# Testing_board_CIDIC_rev_aamaya.net
KiCad netlist of a schematic drawn in EAGLE
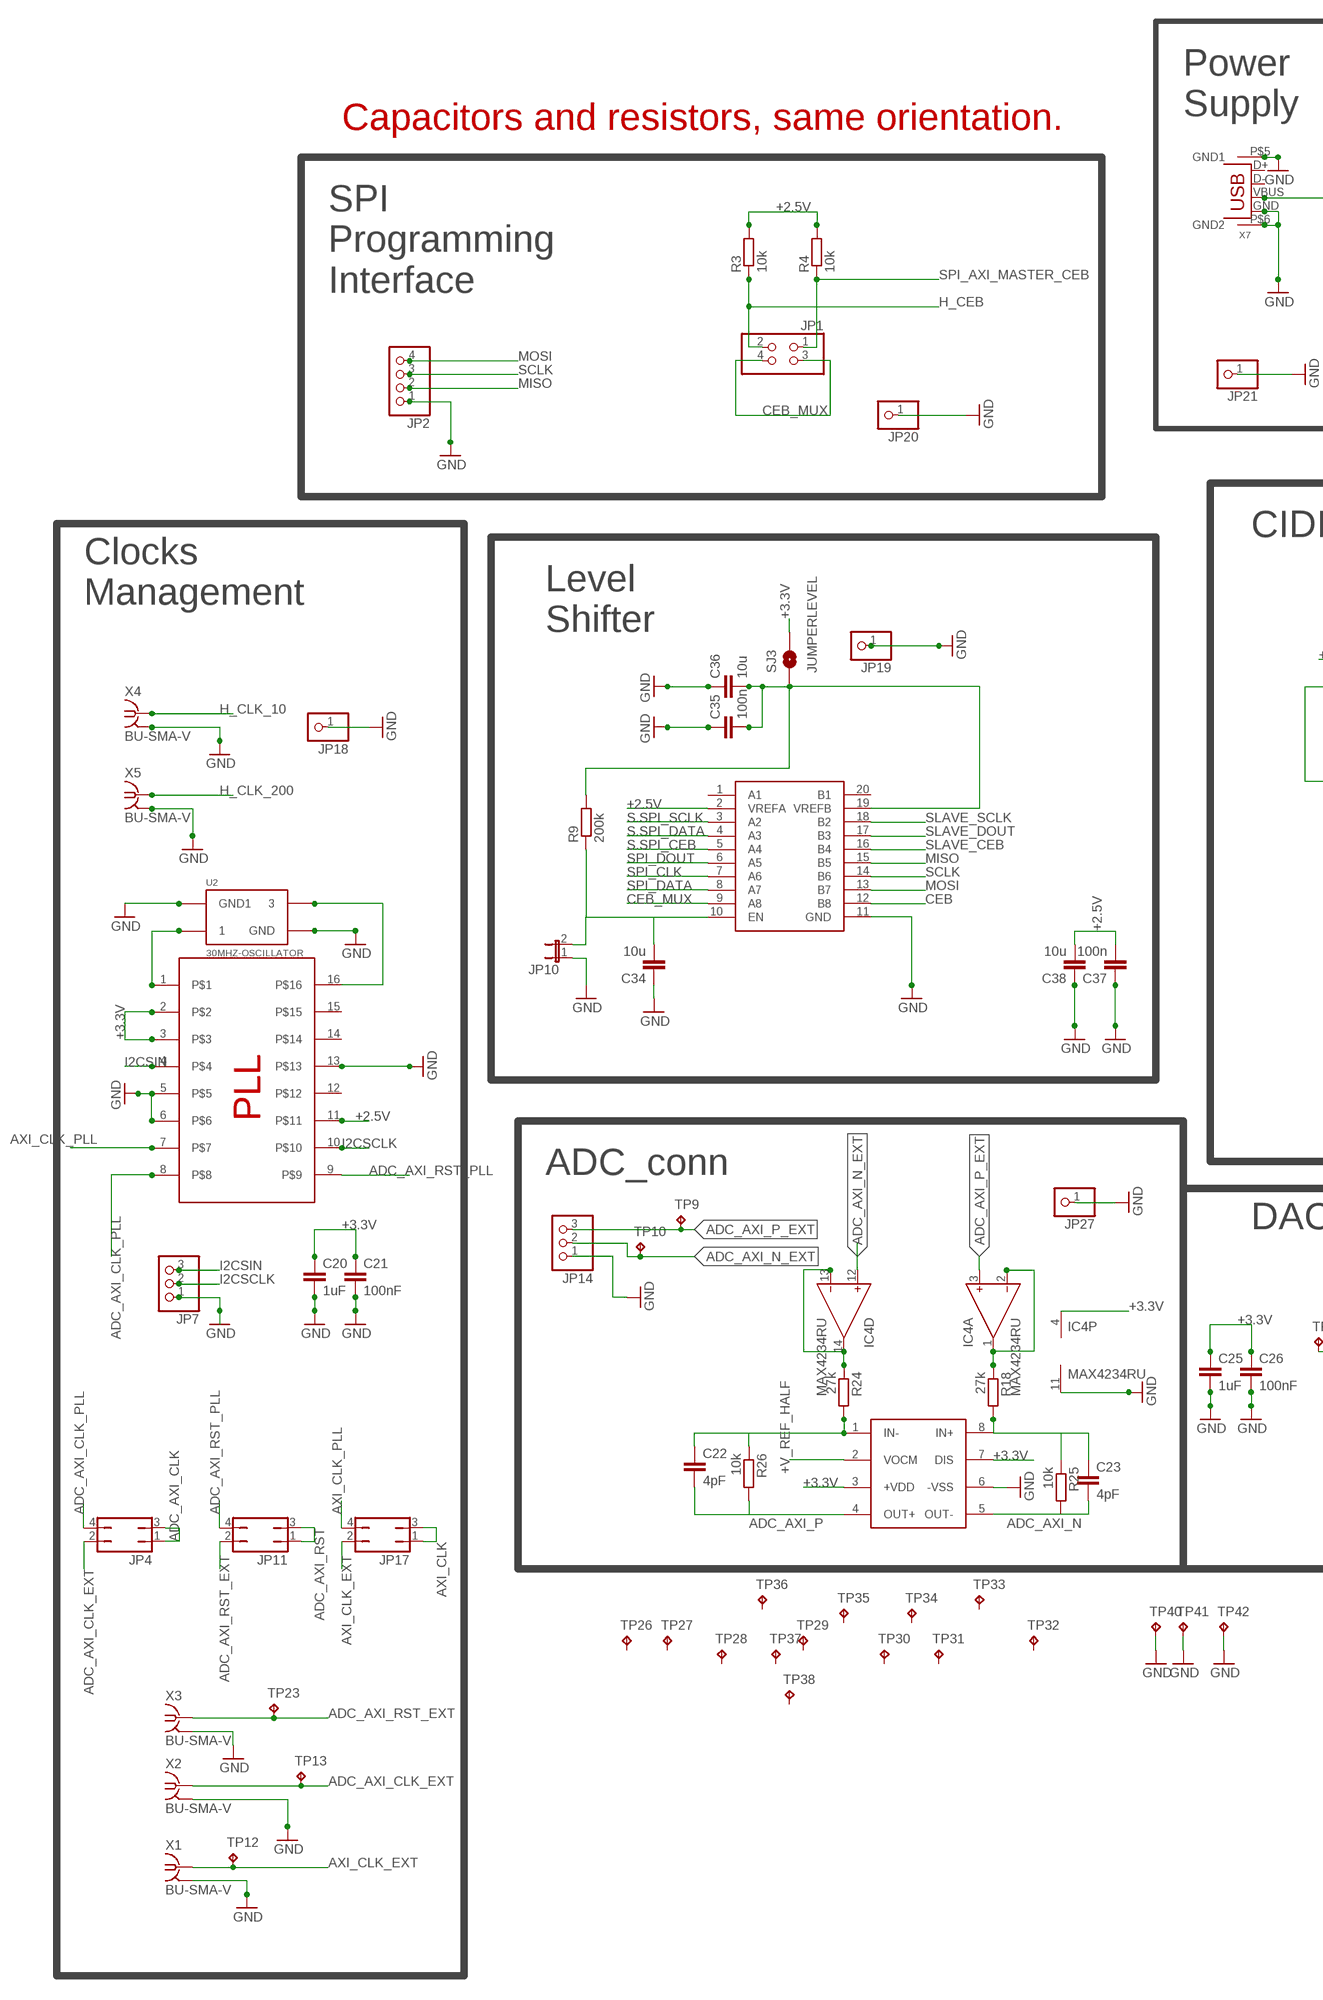
[diagram p0: schematic, sheet 1, part 1 of 2]
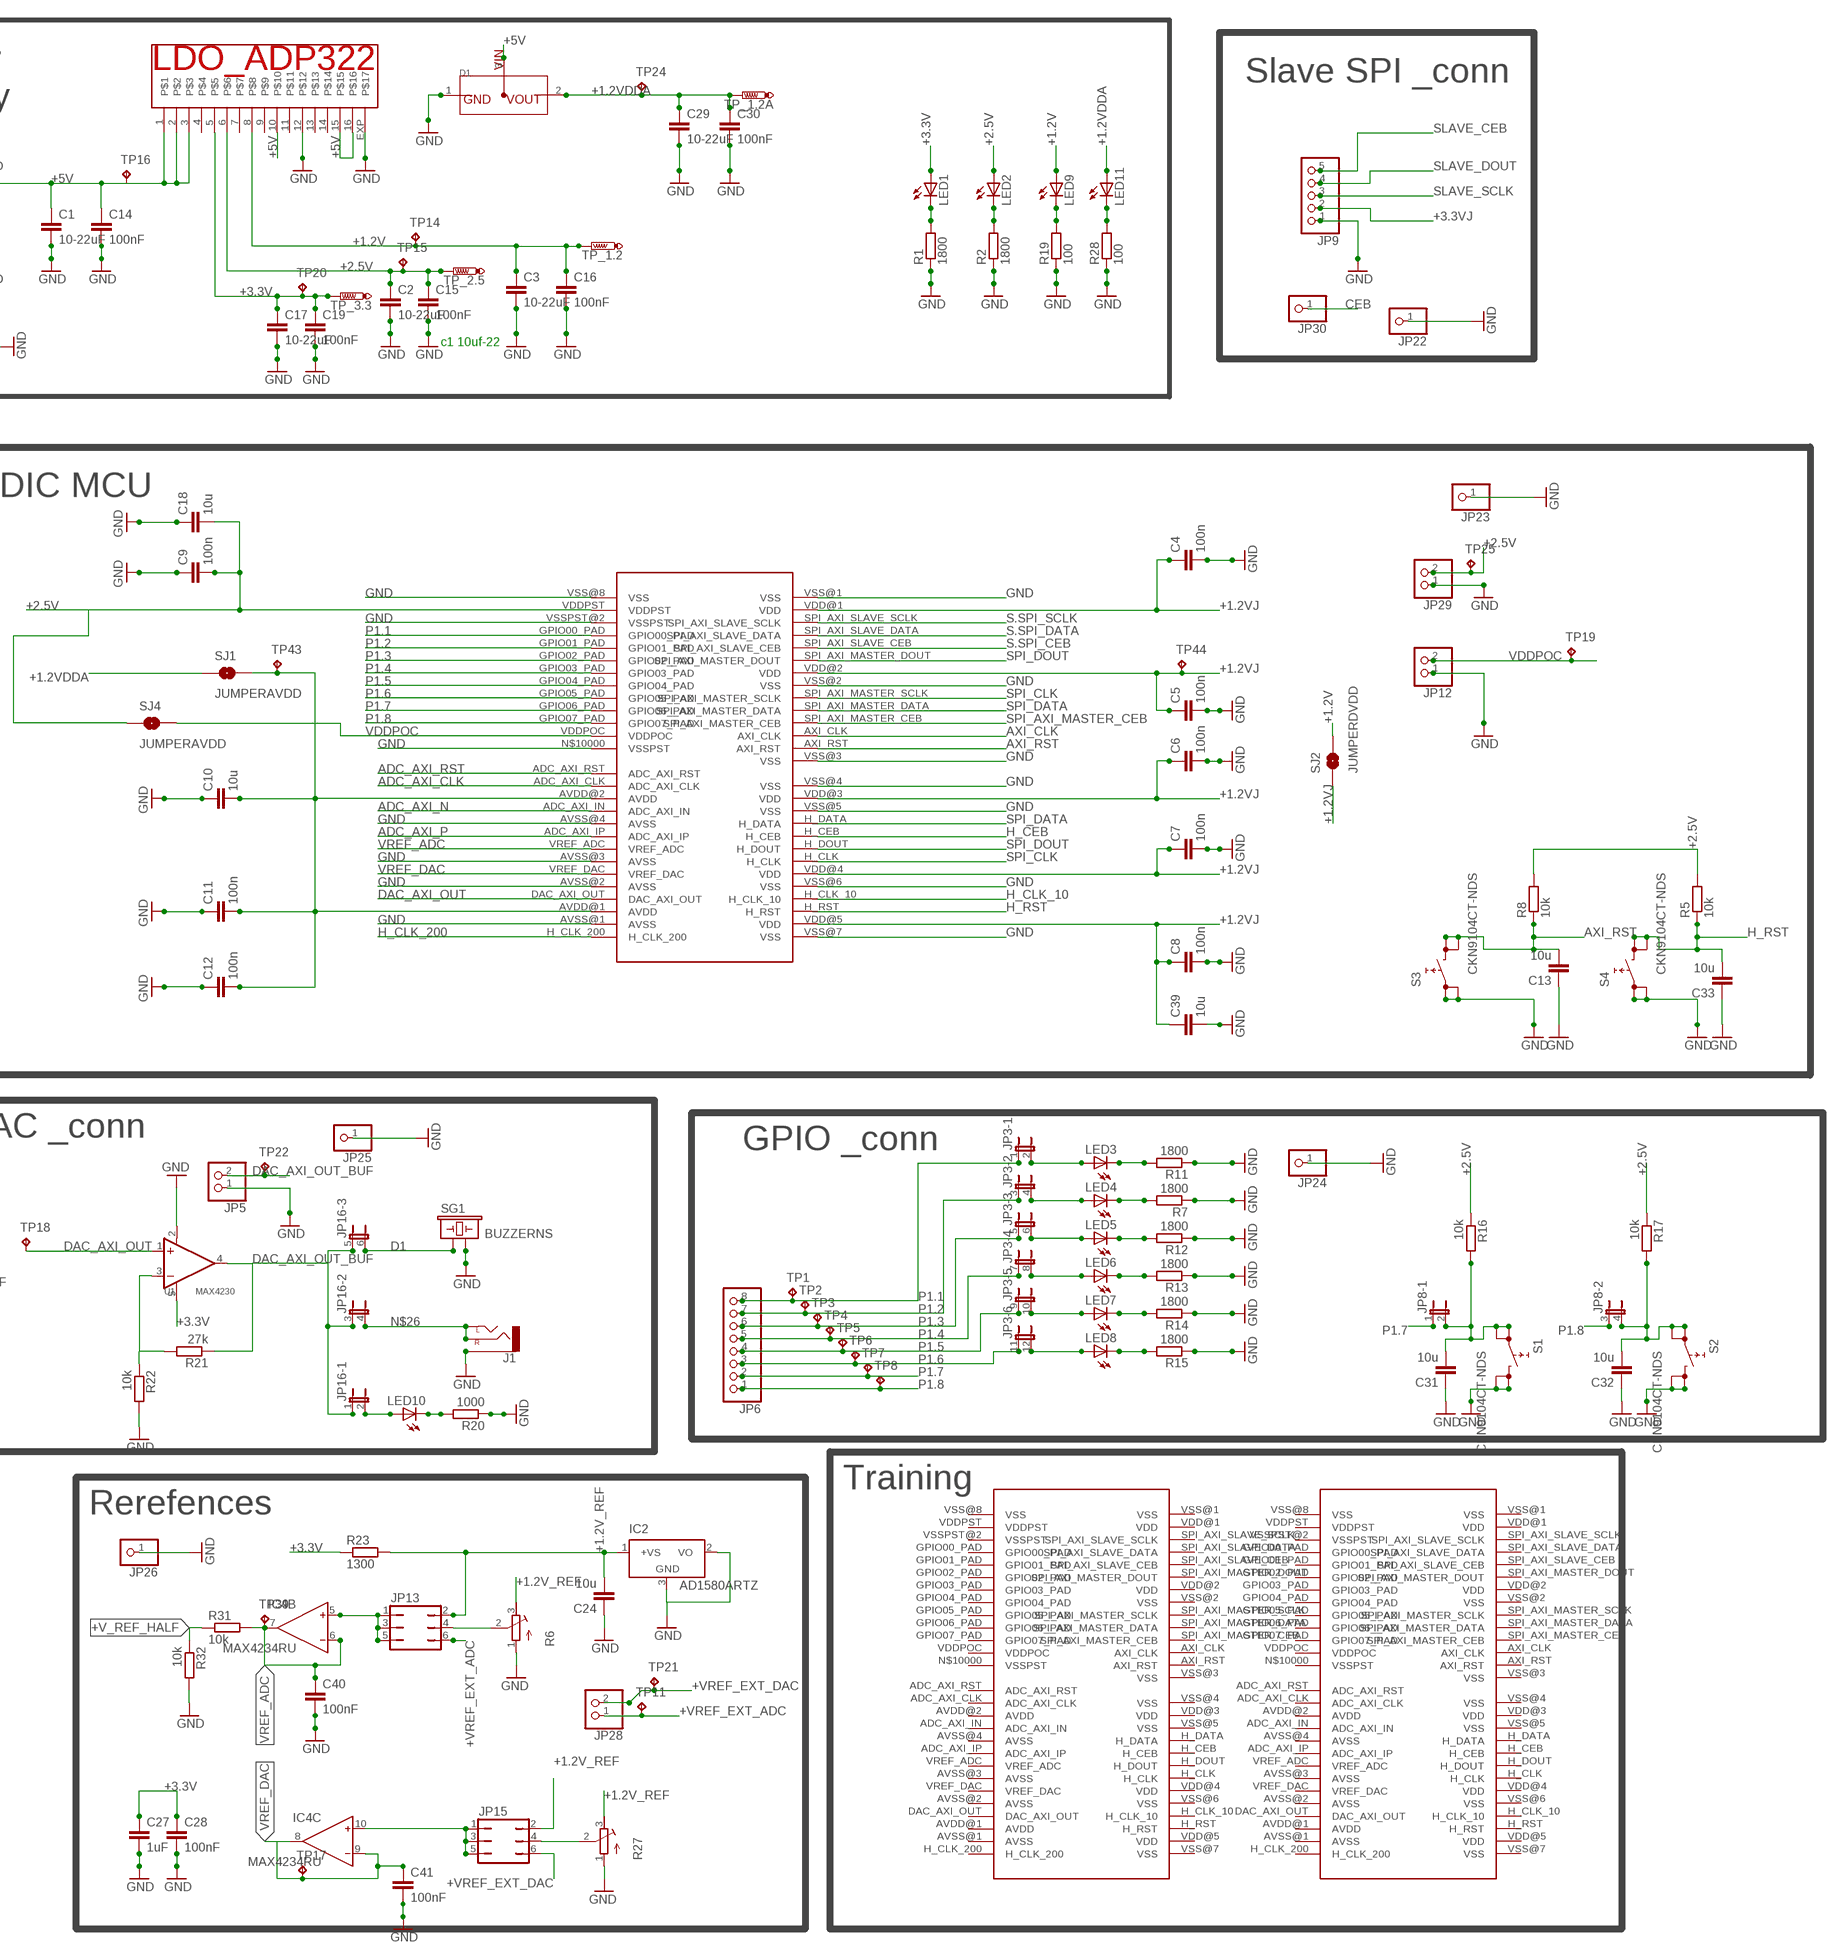
[diagram p1: schematic, sheet 1, part 2 of 2]

(export (version "E")
  (design (tool "Eeschema 10.0.6"))
  (components
    (comp (ref "C1")
      (value "10-22uF")
      (footprint "eagle-import:C0603")
      (libsource (lib "eagle-import") (part "C-EUC0603"))
    )
    (comp (ref "C2")
      (value "10-22uF")
      (footprint "eagle-import:C0603")
      (libsource (lib "eagle-import") (part "C-EUC0603"))
    )
    (comp (ref "C3")
      (value "10-22uF")
      (footprint "eagle-import:C0603")
      (libsource (lib "eagle-import") (part "C-EUC0603"))
    )
    (comp (ref "C4")
      (value "100n")
      (footprint "eagle-import:C0603")
      (libsource (lib "eagle-import") (part "C-EUC0603"))
    )
    (comp (ref "C5")
      (value "100n")
      (footprint "eagle-import:C0603")
      (libsource (lib "eagle-import") (part "C-EUC0603"))
    )
    (comp (ref "C6")
      (value "100n")
      (footprint "eagle-import:C0603")
      (libsource (lib "eagle-import") (part "C-EUC0603"))
    )
    (comp (ref "C7")
      (value "100n")
      (footprint "eagle-import:C0603")
      (libsource (lib "eagle-import") (part "C-EUC0603"))
    )
    (comp (ref "C8")
      (value "100n")
      (footprint "eagle-import:C0603")
      (libsource (lib "eagle-import") (part "C-EUC0603"))
    )
    (comp (ref "C9")
      (value "100n")
      (footprint "eagle-import:C0603")
      (libsource (lib "eagle-import") (part "C-EUC0603"))
    )
    (comp (ref "C10")
      (value "10u")
      (footprint "eagle-import:C0603")
      (libsource (lib "eagle-import") (part "C-EUC0603"))
    )
    (comp (ref "C11")
      (value "100n")
      (footprint "eagle-import:C0603")
      (libsource (lib "eagle-import") (part "C-EUC0603"))
    )
    (comp (ref "C12")
      (value "100n")
      (footprint "eagle-import:C0603")
      (libsource (lib "eagle-import") (part "C-EUC0603"))
    )
    (comp (ref "C13")
      (value "10u")
      (footprint "eagle-import:C0603")
      (libsource (lib "eagle-import") (part "C-EUC0603"))
    )
    (comp (ref "C14")
      (value "100nF")
      (footprint "eagle-import:C0603")
      (libsource (lib "eagle-import") (part "C-EUC0603"))
    )
    (comp (ref "C15")
      (value "100nF")
      (footprint "eagle-import:C0603")
      (libsource (lib "eagle-import") (part "C-EUC0603"))
    )
    (comp (ref "C16")
      (value "100nF")
      (footprint "eagle-import:C0603")
      (libsource (lib "eagle-import") (part "C-EUC0603"))
    )
    (comp (ref "C17")
      (value "10-22uF")
      (footprint "eagle-import:C0603")
      (libsource (lib "eagle-import") (part "C-EUC0603"))
    )
    (comp (ref "C18")
      (value "10u")
      (footprint "eagle-import:C0603")
      (libsource (lib "eagle-import") (part "C-EUC0603"))
    )
    (comp (ref "C19")
      (value "100nF")
      (footprint "eagle-import:C0603")
      (libsource (lib "eagle-import") (part "C-EUC0603"))
    )
    (comp (ref "C20")
      (value "1uF")
      (footprint "eagle-import:C0603")
      (libsource (lib "eagle-import") (part "C-EUC0603"))
    )
    (comp (ref "C21")
      (value "100nF")
      (footprint "eagle-import:C0603")
      (libsource (lib "eagle-import") (part "C-EUC0603"))
    )
    (comp (ref "C22")
      (value "4pF")
      (footprint "eagle-import:C0603")
      (libsource (lib "eagle-import") (part "C-EUC0603"))
    )
    (comp (ref "C23")
      (value "4pF")
      (footprint "eagle-import:C0603")
      (libsource (lib "eagle-import") (part "C-EUC0603"))
    )
    (comp (ref "C24")
      (value "10u")
      (footprint "eagle-import:C0603")
      (libsource (lib "eagle-import") (part "C-EUC0603"))
    )
    (comp (ref "C25")
      (value "1uF")
      (footprint "eagle-import:C0603")
      (libsource (lib "eagle-import") (part "C-EUC0603"))
    )
    (comp (ref "C26")
      (value "100nF")
      (footprint "eagle-import:C0603")
      (libsource (lib "eagle-import") (part "C-EUC0603"))
    )
    (comp (ref "C27")
      (value "1uF")
      (footprint "eagle-import:C0603")
      (libsource (lib "eagle-import") (part "C-EUC0603"))
    )
    (comp (ref "C28")
      (value "100nF")
      (footprint "eagle-import:C0603")
      (libsource (lib "eagle-import") (part "C-EUC0603"))
    )
    (comp (ref "C29")
      (value "10-22uF")
      (footprint "eagle-import:C0603")
      (libsource (lib "eagle-import") (part "C-EUC0603"))
    )
    (comp (ref "C30")
      (value "100nF")
      (footprint "eagle-import:C0603")
      (libsource (lib "eagle-import") (part "C-EUC0603"))
    )
    (comp (ref "C31")
      (value "10u")
      (footprint "eagle-import:C0603")
      (libsource (lib "eagle-import") (part "C-EUC0603"))
    )
    (comp (ref "C32")
      (value "10u")
      (footprint "eagle-import:C0603")
      (libsource (lib "eagle-import") (part "C-EUC0603"))
    )
    (comp (ref "C33")
      (value "10u")
      (footprint "eagle-import:C0603")
      (libsource (lib "eagle-import") (part "C-EUC0603"))
    )
    (comp (ref "C34")
      (value "10u")
      (footprint "eagle-import:C0603")
      (libsource (lib "eagle-import") (part "C-EUC0603"))
    )
    (comp (ref "C35")
      (value "100n")
      (footprint "eagle-import:C0603")
      (libsource (lib "eagle-import") (part "C-EUC0603"))
    )
    (comp (ref "C36")
      (value "10u")
      (footprint "eagle-import:C0603")
      (libsource (lib "eagle-import") (part "C-EUC0603"))
    )
    (comp (ref "C37")
      (value "100n")
      (footprint "eagle-import:C0603")
      (libsource (lib "eagle-import") (part "C-EUC0603"))
    )
    (comp (ref "C38")
      (value "10u")
      (footprint "eagle-import:C0603")
      (libsource (lib "eagle-import") (part "C-EUC0603"))
    )
    (comp (ref "C39")
      (value "10u")
      (footprint "eagle-import:C0603")
      (libsource (lib "eagle-import") (part "C-EUC0603"))
    )
    (comp (ref "C40")
      (value "100nF")
      (footprint "eagle-import:C0603")
      (libsource (lib "eagle-import") (part "C-EUC0603"))
    )
    (comp (ref "C41")
      (value "100nF")
      (footprint "eagle-import:C0603")
      (libsource (lib "eagle-import") (part "C-EUC0603"))
    )
    (comp (ref "D1")
      (value "MCP1700T-1202E/TTCT-ND")
      (footprint "eagle-import:SOT-23")
      (libsource (lib "eagle-import") (part "MCP1700T-1202E/TTCT-ND"))
    )
    (comp (ref "GND")
      (value "ADP322")
      (footprint "eagle-import:LFCSP_LQ-16")
      (libsource (lib "eagle-import") (part "ADP322"))
    )
    (comp (ref "IC2")
      (value "AD1580ARTZ")
      (footprint "eagle-import:SOT23")
      (libsource (lib "eagle-import") (part "LM50"))
    )
    (comp (ref "IC4")
      (value "MAX4234RU")
      (footprint "eagle-import:TSSOP14")
      (fields (field (name "MF") "ALTERA CORPORATION") (field (name "MPN") "AD8609ARUZ"))
      (libsource (lib "eagle-import") (part "MAX4234RU"))
    )
    (comp (ref "J1")
      (value "AUDIO-JACK_DIGIKEYSMD")
      (footprint "eagle-import:STEREOJACK2.5MM_SMD")
      (libsource (lib "eagle-import") (part "AUDIO-JACK_DIGIKEYSMD"))
    )
    (comp (ref "JP1")
      (value "PINHD-2X2")
      (footprint "eagle-import:2X02")
      (libsource (lib "eagle-import") (part "PINHD-2X2"))
    )
    (comp (ref "JP2")
      (value "PINHD-1X4")
      (footprint "eagle-import:1X04")
      (libsource (lib "eagle-import") (part "PINHD-1X4"))
    )
    (comp (ref "JP3")
      (value "JP6QE")
      (footprint "eagle-import:JP6Q")
      (libsource (lib "eagle-import") (part "JP6QE"))
    )
    (comp (ref "JP4")
      (value "JP2Q")
      (footprint "eagle-import:JP2Q")
      (libsource (lib "eagle-import") (part "JP2Q"))
    )
    (comp (ref "JP5")
      (value "PINHD-1X2")
      (footprint "eagle-import:1X02")
      (libsource (lib "eagle-import") (part "PINHD-1X2"))
    )
    (comp (ref "JP6")
      (value "PINHD-1X8")
      (footprint "eagle-import:1X08")
      (libsource (lib "eagle-import") (part "PINHD-1X8"))
    )
    (comp (ref "JP7")
      (value "PINHD-1X3")
      (footprint "eagle-import:1X03")
      (libsource (lib "eagle-import") (part "PINHD-1X3"))
    )
    (comp (ref "JP8")
      (value "JP2QE")
      (footprint "eagle-import:JP2Q")
      (libsource (lib "eagle-import") (part "JP2QE"))
    )
    (comp (ref "JP9")
      (value "PINHD-1X5")
      (footprint "eagle-import:1X05")
      (libsource (lib "eagle-import") (part "PINHD-1X5"))
    )
    (comp (ref "JP10")
      (value "JP1E")
      (footprint "eagle-import:JP1")
      (libsource (lib "eagle-import") (part "JP1E"))
    )
    (comp (ref "JP11")
      (value "JP2Q")
      (footprint "eagle-import:JP2Q")
      (libsource (lib "eagle-import") (part "JP2Q"))
    )
    (comp (ref "JP12")
      (value "PINHD-1X2")
      (footprint "eagle-import:1X02")
      (libsource (lib "eagle-import") (part "PINHD-1X2"))
    )
    (comp (ref "JP13")
      (value "JP3Q")
      (footprint "eagle-import:JP3Q")
      (libsource (lib "eagle-import") (part "JP3Q"))
    )
    (comp (ref "JP14")
      (value "PINHD-1X3")
      (footprint "eagle-import:1X03")
      (libsource (lib "eagle-import") (part "PINHD-1X3"))
    )
    (comp (ref "JP15")
      (value "JP3Q")
      (footprint "eagle-import:JP3Q")
      (libsource (lib "eagle-import") (part "JP3Q"))
    )
    (comp (ref "JP16")
      (value "JP3QE")
      (footprint "eagle-import:JP3Q")
      (libsource (lib "eagle-import") (part "JP3QE"))
    )
    (comp (ref "JP17")
      (value "JP2Q")
      (footprint "eagle-import:JP2Q")
      (libsource (lib "eagle-import") (part "JP2Q"))
    )
    (comp (ref "JP18")
      (value "PINHD-1X1")
      (footprint "eagle-import:1X01")
      (libsource (lib "eagle-import") (part "PINHD-1X1"))
    )
    (comp (ref "JP19")
      (value "PINHD-1X1")
      (footprint "eagle-import:1X01")
      (libsource (lib "eagle-import") (part "PINHD-1X1"))
    )
    (comp (ref "JP20")
      (value "PINHD-1X1")
      (footprint "eagle-import:1X01")
      (libsource (lib "eagle-import") (part "PINHD-1X1"))
    )
    (comp (ref "JP21")
      (value "PINHD-1X1")
      (footprint "eagle-import:1X01")
      (libsource (lib "eagle-import") (part "PINHD-1X1"))
    )
    (comp (ref "JP22")
      (value "PINHD-1X1")
      (footprint "eagle-import:1X01")
      (libsource (lib "eagle-import") (part "PINHD-1X1"))
    )
    (comp (ref "JP23")
      (value "PINHD-1X1")
      (footprint "eagle-import:1X01")
      (libsource (lib "eagle-import") (part "PINHD-1X1"))
    )
    (comp (ref "JP24")
      (value "PINHD-1X1")
      (footprint "eagle-import:1X01")
      (libsource (lib "eagle-import") (part "PINHD-1X1"))
    )
    (comp (ref "JP25")
      (value "PINHD-1X1")
      (footprint "eagle-import:1X01")
      (libsource (lib "eagle-import") (part "PINHD-1X1"))
    )
    (comp (ref "JP26")
      (value "PINHD-1X1")
      (footprint "eagle-import:1X01")
      (libsource (lib "eagle-import") (part "PINHD-1X1"))
    )
    (comp (ref "JP27")
      (value "PINHD-1X1")
      (footprint "eagle-import:1X01")
      (libsource (lib "eagle-import") (part "PINHD-1X1"))
    )
    (comp (ref "JP28")
      (value "PINHD-1X2")
      (footprint "eagle-import:1X02")
      (libsource (lib "eagle-import") (part "PINHD-1X2"))
    )
    (comp (ref "JP29")
      (value "PINHD-1X2")
      (footprint "eagle-import:1X02")
      (libsource (lib "eagle-import") (part "PINHD-1X2"))
    )
    (comp (ref "JP30")
      (value "PINHD-1X1")
      (footprint "eagle-import:1X01")
      (libsource (lib "eagle-import") (part "PINHD-1X1"))
    )
    (comp (ref "LED1")
      (value "LEDSML0805")
      (footprint "eagle-import:SML0805")
      (libsource (lib "eagle-import") (part "LEDSML0805"))
    )
    (comp (ref "LED2")
      (value "LEDSML0805")
      (footprint "eagle-import:SML0805")
      (libsource (lib "eagle-import") (part "LEDSML0805"))
    )
    (comp (ref "LED3")
      (value "LEDCHIPLED_0805")
      (footprint "eagle-import:CHIPLED_0805")
      (libsource (lib "eagle-import") (part "LEDCHIPLED_0805"))
    )
    (comp (ref "LED4")
      (value "LEDCHIPLED_0805")
      (footprint "eagle-import:CHIPLED_0805")
      (libsource (lib "eagle-import") (part "LEDCHIPLED_0805"))
    )
    (comp (ref "LED5")
      (value "LEDCHIPLED_0805")
      (footprint "eagle-import:CHIPLED_0805")
      (libsource (lib "eagle-import") (part "LEDCHIPLED_0805"))
    )
    (comp (ref "LED6")
      (value "LEDCHIPLED_0805")
      (footprint "eagle-import:CHIPLED_0805")
      (libsource (lib "eagle-import") (part "LEDCHIPLED_0805"))
    )
    (comp (ref "LED7")
      (value "LEDCHIPLED_0805")
      (footprint "eagle-import:CHIPLED_0805")
      (libsource (lib "eagle-import") (part "LEDCHIPLED_0805"))
    )
    (comp (ref "LED8")
      (value "LEDCHIPLED_0805")
      (footprint "eagle-import:CHIPLED_0805")
      (libsource (lib "eagle-import") (part "LEDCHIPLED_0805"))
    )
    (comp (ref "LED9")
      (value "LEDSML0805")
      (footprint "eagle-import:SML0805")
      (libsource (lib "eagle-import") (part "LEDSML0805"))
    )
    (comp (ref "LED10")
      (value "LEDSML0805")
      (footprint "eagle-import:SML0805")
      (libsource (lib "eagle-import") (part "LEDSML0805"))
    )
    (comp (ref "LED11")
      (value "LEDSML0805")
      (footprint "eagle-import:SML0805")
      (libsource (lib "eagle-import") (part "LEDSML0805"))
    )
    (comp (ref "R1")
      (value "1800")
      (footprint "eagle-import:R0603")
      (libsource (lib "eagle-import") (part "R-EU_R0603"))
    )
    (comp (ref "R2")
      (value "1800")
      (footprint "eagle-import:R0603")
      (libsource (lib "eagle-import") (part "R-EU_R0603"))
    )
    (comp (ref "R3")
      (value "10k")
      (footprint "eagle-import:R0603")
      (libsource (lib "eagle-import") (part "R-EU_R0603"))
    )
    (comp (ref "R4")
      (value "10k")
      (footprint "eagle-import:R0603")
      (libsource (lib "eagle-import") (part "R-EU_R0603"))
    )
    (comp (ref "R5")
      (value "10k")
      (footprint "eagle-import:R0603")
      (libsource (lib "eagle-import") (part "R-EU_R0603"))
    )
    (comp (ref "R6")
      (value "R-TRIMM4G/J")
      (footprint "eagle-import:RTRIM4G_J")
      (libsource (lib "eagle-import") (part "R-TRIMM4G/J"))
    )
    (comp (ref "R7")
      (value "1800")
      (footprint "eagle-import:R0603")
      (libsource (lib "eagle-import") (part "R-EU_R0603"))
    )
    (comp (ref "R8")
      (value "10k")
      (footprint "eagle-import:R0603")
      (libsource (lib "eagle-import") (part "R-EU_R0603"))
    )
    (comp (ref "R9")
      (value "200k")
      (footprint "eagle-import:R0603")
      (libsource (lib "eagle-import") (part "R-EU_R0603"))
    )
    (comp (ref "R11")
      (value "1800")
      (footprint "eagle-import:R0603")
      (libsource (lib "eagle-import") (part "R-EU_R0603"))
    )
    (comp (ref "R12")
      (value "1800")
      (footprint "eagle-import:R0603")
      (libsource (lib "eagle-import") (part "R-EU_R0603"))
    )
    (comp (ref "R13")
      (value "1800")
      (footprint "eagle-import:R0603")
      (libsource (lib "eagle-import") (part "R-EU_R0603"))
    )
    (comp (ref "R14")
      (value "1800")
      (footprint "eagle-import:R0603")
      (libsource (lib "eagle-import") (part "R-EU_R0603"))
    )
    (comp (ref "R15")
      (value "1800")
      (footprint "eagle-import:R0603")
      (libsource (lib "eagle-import") (part "R-EU_R0603"))
    )
    (comp (ref "R16")
      (value "10k")
      (footprint "eagle-import:R0603")
      (libsource (lib "eagle-import") (part "R-EU_R0603"))
    )
    (comp (ref "R17")
      (value "10k")
      (footprint "eagle-import:R0603")
      (libsource (lib "eagle-import") (part "R-EU_R0603"))
    )
    (comp (ref "R18")
      (value "27k")
      (footprint "eagle-import:R0603")
      (libsource (lib "eagle-import") (part "R-EU_R0603"))
    )
    (comp (ref "R19")
      (value "100")
      (footprint "eagle-import:R0603")
      (libsource (lib "eagle-import") (part "R-EU_R0603"))
    )
    (comp (ref "R20")
      (value "1000")
      (footprint "eagle-import:R0603")
      (libsource (lib "eagle-import") (part "R-EU_R0603"))
    )
    (comp (ref "R21")
      (value "27k")
      (footprint "eagle-import:R0603")
      (libsource (lib "eagle-import") (part "R-EU_R0603"))
    )
    (comp (ref "R22")
      (value "10k")
      (footprint "eagle-import:R0603")
      (libsource (lib "eagle-import") (part "R-EU_R0603"))
    )
    (comp (ref "R23")
      (value "1300")
      (footprint "eagle-import:R0603")
      (libsource (lib "eagle-import") (part "R-EU_R0603"))
    )
    (comp (ref "R24")
      (value "27k")
      (footprint "eagle-import:R0603")
      (libsource (lib "eagle-import") (part "R-EU_R0603"))
    )
    (comp (ref "R25")
      (value "10k")
      (footprint "eagle-import:R0603")
      (libsource (lib "eagle-import") (part "R-EU_R0603"))
    )
    (comp (ref "R26")
      (value "10k")
      (footprint "eagle-import:R0603")
      (libsource (lib "eagle-import") (part "R-EU_R0603"))
    )
    (comp (ref "R27")
      (value "R-TRIMM4G/J")
      (footprint "eagle-import:RTRIM4G_J")
      (libsource (lib "eagle-import") (part "R-TRIMM4G/J"))
    )
    (comp (ref "R28")
      (value "100")
      (footprint "eagle-import:R0603")
      (libsource (lib "eagle-import") (part "R-EU_R0603"))
    )
    (comp (ref "R31")
      (value "10k")
      (footprint "eagle-import:R0603")
      (libsource (lib "eagle-import") (part "R-EU_R0603"))
    )
    (comp (ref "R32")
      (value "10k")
      (footprint "eagle-import:R0603")
      (libsource (lib "eagle-import") (part "R-EU_R0603"))
    )
    (comp (ref "S1")
      (value "CKN9104CT-NDS")
      (footprint "eagle-import:SKHMPXE010")
      (libsource (lib "eagle-import") (part "CKN9104CT-NDS"))
    )
    (comp (ref "S2")
      (value "CKN9104CT-NDS")
      (footprint "eagle-import:SKHMPXE010")
      (libsource (lib "eagle-import") (part "CKN9104CT-NDS"))
    )
    (comp (ref "S3")
      (value "CKN9104CT-NDS")
      (footprint "eagle-import:SKHMPXE010")
      (libsource (lib "eagle-import") (part "CKN9104CT-NDS"))
    )
    (comp (ref "S4")
      (value "CKN9104CT-NDS")
      (footprint "eagle-import:SKHMPXE010")
      (libsource (lib "eagle-import") (part "CKN9104CT-NDS"))
    )
    (comp (ref "SG1")
      (value "BUZZERNS")
      (footprint "eagle-import:BUZZER-12MM-NS")
      (libsource (lib "eagle-import") (part "BUZZERNS"))
    )
    (comp (ref "SJ1")
      (value "JUMPERAVDD")
      (footprint "eagle-import:SJ_ROUND")
      (libsource (lib "eagle-import") (part "SOLDERJUMPERROUND"))
    )
    (comp (ref "SJ2")
      (value "JUMPERDVDD")
      (footprint "eagle-import:SJ_ROUND")
      (libsource (lib "eagle-import") (part "SOLDERJUMPERROUND"))
    )
    (comp (ref "SJ3")
      (value "JUMPERLEVEL")
      (footprint "eagle-import:SJ_ROUND")
      (libsource (lib "eagle-import") (part "SOLDERJUMPERROUND"))
    )
    (comp (ref "SJ4")
      (value "JUMPERAVDD")
      (footprint "eagle-import:SJ_ROUND")
      (libsource (lib "eagle-import") (part "SOLDERJUMPERROUND"))
    )
    (comp (ref "TP1")
      (value "TPTP20R")
      (footprint "eagle-import:TP20R")
      (libsource (lib "eagle-import") (part "TPTP20R"))
    )
    (comp (ref "TP2")
      (value "TPTP20R")
      (footprint "eagle-import:TP20R")
      (libsource (lib "eagle-import") (part "TPTP20R"))
    )
    (comp (ref "TP3")
      (value "TPTP20R")
      (footprint "eagle-import:TP20R")
      (libsource (lib "eagle-import") (part "TPTP20R"))
    )
    (comp (ref "TP4")
      (value "TPTP20R")
      (footprint "eagle-import:TP20R")
      (libsource (lib "eagle-import") (part "TPTP20R"))
    )
    (comp (ref "TP5")
      (value "TPTP20R")
      (footprint "eagle-import:TP20R")
      (libsource (lib "eagle-import") (part "TPTP20R"))
    )
    (comp (ref "TP6")
      (value "TPTP20R")
      (footprint "eagle-import:TP20R")
      (libsource (lib "eagle-import") (part "TPTP20R"))
    )
    (comp (ref "TP7")
      (value "TPTP20R")
      (footprint "eagle-import:TP20R")
      (libsource (lib "eagle-import") (part "TPTP20R"))
    )
    (comp (ref "TP8")
      (value "TPTP20R")
      (footprint "eagle-import:TP20R")
      (libsource (lib "eagle-import") (part "TPTP20R"))
    )
    (comp (ref "TP9")
      (value "TPTP20R")
      (footprint "eagle-import:TP20R")
      (libsource (lib "eagle-import") (part "TPTP20R"))
    )
    (comp (ref "TP10")
      (value "TPTP20R")
      (footprint "eagle-import:TP20R")
      (libsource (lib "eagle-import") (part "TPTP20R"))
    )
    (comp (ref "TP11")
      (value "TPTP20R")
      (footprint "eagle-import:TP20R")
      (libsource (lib "eagle-import") (part "TPTP20R"))
    )
    (comp (ref "TP12")
      (value "TPTP20R")
      (footprint "eagle-import:TP20R")
      (libsource (lib "eagle-import") (part "TPTP20R"))
    )
    (comp (ref "TP13")
      (value "TPTP20R")
      (footprint "eagle-import:TP20R")
      (libsource (lib "eagle-import") (part "TPTP20R"))
    )
    (comp (ref "TP14")
      (value "TPTP20R")
      (footprint "eagle-import:TP20R")
      (libsource (lib "eagle-import") (part "TPTP20R"))
    )
    (comp (ref "TP15")
      (value "TPTP20R")
      (footprint "eagle-import:TP20R")
      (libsource (lib "eagle-import") (part "TPTP20R"))
    )
    (comp (ref "TP16")
      (value "TPTP20R")
      (footprint "eagle-import:TP20R")
      (libsource (lib "eagle-import") (part "TPTP20R"))
    )
    (comp (ref "TP17")
      (value "TPTP20R")
      (footprint "eagle-import:TP20R")
      (libsource (lib "eagle-import") (part "TPTP20R"))
    )
    (comp (ref "TP18")
      (value "TPTP20R")
      (footprint "eagle-import:TP20R")
      (libsource (lib "eagle-import") (part "TPTP20R"))
    )
    (comp (ref "TP19")
      (value "TPTP20R")
      (footprint "eagle-import:TP20R")
      (libsource (lib "eagle-import") (part "TPTP20R"))
    )
    (comp (ref "TP20")
      (value "TPTP20R")
      (footprint "eagle-import:TP20R")
      (libsource (lib "eagle-import") (part "TPTP20R"))
    )
    (comp (ref "TP21")
      (value "TPTP20R")
      (footprint "eagle-import:TP20R")
      (libsource (lib "eagle-import") (part "TPTP20R"))
    )
    (comp (ref "TP22")
      (value "TPTP20R")
      (footprint "eagle-import:TP20R")
      (libsource (lib "eagle-import") (part "TPTP20R"))
    )
    (comp (ref "TP23")
      (value "TPTP20R")
      (footprint "eagle-import:TP20R")
      (libsource (lib "eagle-import") (part "TPTP20R"))
    )
    (comp (ref "TP24")
      (value "TPTP20R")
      (footprint "eagle-import:TP20R")
      (libsource (lib "eagle-import") (part "TPTP20R"))
    )
    (comp (ref "TP25")
      (value "TPTP20R")
      (footprint "eagle-import:TP20R")
      (libsource (lib "eagle-import") (part "TPTP20R"))
    )
    (comp (ref "TP26")
      (value "TPTP08R")
      (footprint "eagle-import:TP08R")
      (libsource (lib "eagle-import") (part "TPTP08R"))
    )
    (comp (ref "TP27")
      (value "TPTP08R")
      (footprint "eagle-import:TP08R")
      (libsource (lib "eagle-import") (part "TPTP08R"))
    )
    (comp (ref "TP28")
      (value "TPTP08R")
      (footprint "eagle-import:TP08R")
      (libsource (lib "eagle-import") (part "TPTP08R"))
    )
    (comp (ref "TP29")
      (value "TPTP08R")
      (footprint "eagle-import:TP08R")
      (libsource (lib "eagle-import") (part "TPTP08R"))
    )
    (comp (ref "TP30")
      (value "TPTP08R")
      (footprint "eagle-import:TP08R")
      (libsource (lib "eagle-import") (part "TPTP08R"))
    )
    (comp (ref "TP31")
      (value "TPTP08R")
      (footprint "eagle-import:TP08R")
      (libsource (lib "eagle-import") (part "TPTP08R"))
    )
    (comp (ref "TP32")
      (value "TPTP08R")
      (footprint "eagle-import:TP08R")
      (libsource (lib "eagle-import") (part "TPTP08R"))
    )
    (comp (ref "TP33")
      (value "TPTP08R")
      (footprint "eagle-import:TP08R")
      (libsource (lib "eagle-import") (part "TPTP08R"))
    )
    (comp (ref "TP34")
      (value "TPTP08R")
      (footprint "eagle-import:TP08R")
      (libsource (lib "eagle-import") (part "TPTP08R"))
    )
    (comp (ref "TP35")
      (value "TPTP08R")
      (footprint "eagle-import:TP08R")
      (libsource (lib "eagle-import") (part "TPTP08R"))
    )
    (comp (ref "TP36")
      (value "TPTP08R")
      (footprint "eagle-import:TP08R")
      (libsource (lib "eagle-import") (part "TPTP08R"))
    )
    (comp (ref "TP37")
      (value "TPTP08R")
      (footprint "eagle-import:TP08R")
      (libsource (lib "eagle-import") (part "TPTP08R"))
    )
    (comp (ref "TP38")
      (value "TPTP08R")
      (footprint "eagle-import:TP08R")
      (libsource (lib "eagle-import") (part "TPTP08R"))
    )
    (comp (ref "TP39")
      (value "TPTP20R")
      (footprint "eagle-import:TP20R")
      (libsource (lib "eagle-import") (part "TPTP20R"))
    )
    (comp (ref "TP40")
      (value "TPTP20R")
      (footprint "eagle-import:TP20R")
      (libsource (lib "eagle-import") (part "TPTP20R"))
    )
    (comp (ref "TP41")
      (value "TPTP20R")
      (footprint "eagle-import:TP20R")
      (libsource (lib "eagle-import") (part "TPTP20R"))
    )
    (comp (ref "TP42")
      (value "TPTP20R")
      (footprint "eagle-import:TP20R")
      (libsource (lib "eagle-import") (part "TPTP20R"))
    )
    (comp (ref "TP43")
      (value "TPTP20R")
      (footprint "eagle-import:TP20R")
      (libsource (lib "eagle-import") (part "TPTP20R"))
    )
    (comp (ref "TP44")
      (value "TPTP20R")
      (footprint "eagle-import:TP20R")
      (libsource (lib "eagle-import") (part "TPTP20R"))
    )
    (comp (ref "TP_1.2")
      (value "PTR1B1,27")
      (footprint "eagle-import:B1,27")
      (libsource (lib "eagle-import") (part "PTR1B1,27"))
    )
    (comp (ref "TP_1.2A")
      (value "PTR1B1,27")
      (footprint "eagle-import:B1,27")
      (libsource (lib "eagle-import") (part "PTR1B1,27"))
    )
    (comp (ref "TP_2.5")
      (value "PTR1B1,27")
      (footprint "eagle-import:B1,27")
      (libsource (lib "eagle-import") (part "PTR1B1,27"))
    )
    (comp (ref "TP_3.3")
      (value "PTR1B1,27")
      (footprint "eagle-import:B1,27")
      (libsource (lib "eagle-import") (part "PTR1B1,27"))
    )
    (comp (ref "U$1")
      (value "CIDIC_AXI_UC_TEST_DIE")
      (footprint "eagle-import:CIDIC_AXI_UC_TEST_DIE")
      (libsource (lib "eagle-import") (part "CIDIC_AXI_UC_TEST_DIE"))
    )
    (comp (ref "U$3")
      (value "LEVEL_SHIFTER_8")
      (footprint "eagle-import:TSSOP20")
      (libsource (lib "eagle-import") (part "LEVEL_SHIFTER_8"))
    )
    (comp (ref "U$4")
      (value "CY22150KFZXC")
      (footprint "eagle-import:TSSOP16")
      (libsource (lib "eagle-import") (part "CY22150KFZXC"))
    )
    (comp (ref "U$5")
      (value "ADA4940")
      (footprint "eagle-import:SO8")
      (libsource (lib "eagle-import") (part "ADA4940"))
    )
    (comp (ref "U$6")
      (value "CIDIC_AXI_UC_TEST_DIE")
      (footprint "eagle-import:CIDIC_AXI_UC_TEST_DIE")
      (libsource (lib "eagle-import") (part "CIDIC_AXI_UC_TEST_DIE"))
    )
    (comp (ref "U$7")
      (value "CIDIC_AXI_UC_TEST_DIE")
      (footprint "eagle-import:CIDIC_AXI_UC_TEST_DIE")
      (libsource (lib "eagle-import") (part "CIDIC_AXI_UC_TEST_DIE"))
    )
    (comp (ref "U1")
      (value "MAX4230")
      (footprint "eagle-import:SC-70-5")
      (fields (field (name "MPN") "LMV321IDCKR"))
      (libsource (lib "eagle-import") (part "MAX4230"))
    )
    (comp (ref "U2")
      (value "30MHZ-OSCILLATOR")
      (footprint "eagle-import:5X3.2")
      (libsource (lib "eagle-import") (part "30MHZ-OSCILLATOR"))
    )
    (comp (ref "X1")
      (value "BU-SMA-V")
      (footprint "eagle-import:BU-SMA-V")
      (libsource (lib "eagle-import") (part "BU-SMA-V"))
    )
    (comp (ref "X2")
      (value "BU-SMA-V")
      (footprint "eagle-import:BU-SMA-V")
      (libsource (lib "eagle-import") (part "BU-SMA-V"))
    )
    (comp (ref "X3")
      (value "BU-SMA-V")
      (footprint "eagle-import:BU-SMA-V")
      (libsource (lib "eagle-import") (part "BU-SMA-V"))
    )
    (comp (ref "X4")
      (value "BU-SMA-V")
      (footprint "eagle-import:BU-SMA-V")
      (libsource (lib "eagle-import") (part "BU-SMA-V"))
    )
    (comp (ref "X5")
      (value "BU-SMA-V")
      (footprint "eagle-import:BU-SMA-V")
      (libsource (lib "eagle-import") (part "BU-SMA-V"))
    )
    (comp (ref "X7")
      (value "USB-A-H")
      (footprint "eagle-import:USB-A-H")
      (libsource (lib "eagle-import") (part "USB-A-H"))
    )
  )
  (nets
    (net (code "1") (name "+V_REF_HALF") (class "Default")
      (node (ref "R31") (pin "1") (pinfunction "1_1") (pintype "passive"))
      (node (ref "R32") (pin "1") (pinfunction "1_1") (pintype "passive"))
      (node (ref "U$5") (pin "2") (pinfunction "VOCM_2") (pintype "bidirectional"))
    )
    (net (code "2") (name "/+1.2V") (class "Default")
      (node (ref "C16") (pin "1") (pinfunction "1_1") (pintype "passive"))
      (node (ref "C3") (pin "1") (pinfunction "1_1") (pintype "passive"))
      (node (ref "GND") (pin "8") (pinfunction "P$8_8") (pintype "bidirectional"))
      (node (ref "LED9") (pin "A") (pinfunction "A_A") (pintype "passive"))
      (node (ref "SJ2") (pin "2") (pinfunction "2_2") (pintype "passive"))
      (node (ref "TP14") (pin "TP") (pinfunction "TP_TP") (pintype "input"))
      (node (ref "TP_1.2") (pin "TP") (pinfunction "TP_TP") (pintype "input"))
    )
    (net (code "3") (name "/+1.2VDDA") (class "Default")
      (node (ref "C29") (pin "1") (pinfunction "1_1") (pintype "passive"))
      (node (ref "C30") (pin "1") (pinfunction "1_1") (pintype "passive"))
      (node (ref "D1") (pin "2") (pinfunction "VOUT_2") (pintype "bidirectional"))
      (node (ref "LED11") (pin "A") (pinfunction "A_A") (pintype "passive"))
      (node (ref "SJ1") (pin "1") (pinfunction "1_1") (pintype "passive"))
      (node (ref "TP24") (pin "TP") (pinfunction "TP_TP") (pintype "input"))
      (node (ref "TP_1.2A") (pin "TP") (pinfunction "TP_TP") (pintype "input"))
    )
    (net (code "4") (name "/+1.2VJ") (class "Default")
      (node (ref "C39") (pin "1") (pinfunction "1_1") (pintype "passive"))
      (node (ref "C4") (pin "1") (pinfunction "1_1") (pintype "passive"))
      (node (ref "C5") (pin "1") (pinfunction "1_1") (pintype "passive"))
      (node (ref "C6") (pin "1") (pinfunction "1_1") (pintype "passive"))
      (node (ref "C7") (pin "1") (pinfunction "1_1") (pintype "passive"))
      (node (ref "C8") (pin "1") (pinfunction "1_1") (pintype "passive"))
      (node (ref "SJ2") (pin "1") (pinfunction "1_1") (pintype "passive"))
      (node (ref "TP44") (pin "TP") (pinfunction "TP_TP") (pintype "input"))
      (node (ref "U$1") (pin "VDD@1") (pinfunction "VDD_VDD@1") (pintype "bidirectional"))
      (node (ref "U$1") (pin "VDD@2") (pinfunction "VDD_VDD@2") (pintype "bidirectional"))
      (node (ref "U$1") (pin "VDD@3") (pinfunction "VDD_VDD@3") (pintype "bidirectional"))
      (node (ref "U$1") (pin "VDD@4") (pinfunction "VDD_VDD@4") (pintype "bidirectional"))
      (node (ref "U$1") (pin "VDD@5") (pinfunction "VDD_VDD@5") (pintype "bidirectional"))
    )
    (net (code "5") (name "/+1.2V_REF") (class "Default")
      (node (ref "C24") (pin "2") (pinfunction "2_2") (pintype "passive"))
      (node (ref "IC2") (pin "1") (pinfunction "+VS_1") (pintype "input"))
      (node (ref "JP13") (pin "2") (pinfunction "2_2") (pintype "passive"))
      (node (ref "JP15") (pin "2") (pinfunction "2_2") (pintype "passive"))
      (node (ref "R23") (pin "2") (pinfunction "2_2") (pintype "passive"))
      (node (ref "R27") (pin "3") (pinfunction "E_3") (pintype "passive"))
      (node (ref "R6") (pin "3") (pinfunction "E_3") (pintype "passive"))
    )
    (net (code "6") (name "/+2.5V") (class "Default")
      (node (ref "C15") (pin "1") (pinfunction "1_1") (pintype "passive"))
      (node (ref "C18") (pin "2") (pinfunction "2_2") (pintype "passive"))
      (node (ref "C2") (pin "1") (pinfunction "1_1") (pintype "passive"))
      (node (ref "C37") (pin "2") (pinfunction "2_2") (pintype "passive"))
      (node (ref "C38") (pin "2") (pinfunction "2_2") (pintype "passive"))
      (node (ref "C9") (pin "2") (pinfunction "2_2") (pintype "passive"))
      (node (ref "GND") (pin "6") (pinfunction "P$6_6") (pintype "bidirectional"))
      (node (ref "JP29") (pin "2") (pinfunction "2_2") (pintype "passive"))
      (node (ref "LED2") (pin "A") (pinfunction "A_A") (pintype "passive"))
      (node (ref "R16") (pin "1") (pinfunction "1_1") (pintype "passive"))
      (node (ref "R17") (pin "1") (pinfunction "1_1") (pintype "passive"))
      (node (ref "R3") (pin "2") (pinfunction "2_2") (pintype "passive"))
      (node (ref "R4") (pin "2") (pinfunction "2_2") (pintype "passive"))
      (node (ref "R5") (pin "2") (pinfunction "2_2") (pintype "passive"))
      (node (ref "R8") (pin "2") (pinfunction "2_2") (pintype "passive"))
      (node (ref "SJ4") (pin "1") (pinfunction "1_1") (pintype "passive"))
      (node (ref "TP15") (pin "TP") (pinfunction "TP_TP") (pintype "input"))
      (node (ref "TP25") (pin "TP") (pinfunction "TP_TP") (pintype "input"))
      (node (ref "TP_2.5") (pin "TP") (pinfunction "TP_TP") (pintype "input"))
      (node (ref "U$1") (pin "VDDPST") (pinfunction "VDDPST_VDDPST") (pintype "bidirectional"))
      (node (ref "U$3") (pin "2") (pinfunction "VREFA_2") (pintype "bidirectional"))
      (node (ref "U$4") (pin "11") (pinfunction "P$11_11") (pintype "bidirectional"))
    )
    (net (code "7") (name "/+3.3V") (class "Default")
      (node (ref "C17") (pin "1") (pinfunction "1_1") (pintype "passive"))
      (node (ref "C19") (pin "1") (pinfunction "1_1") (pintype "passive"))
      (node (ref "C20") (pin "1") (pinfunction "1_1") (pintype "passive"))
      (node (ref "C21") (pin "1") (pinfunction "1_1") (pintype "passive"))
      (node (ref "C25") (pin "1") (pinfunction "1_1") (pintype "passive"))
      (node (ref "C26") (pin "1") (pinfunction "1_1") (pintype "passive"))
      (node (ref "C27") (pin "1") (pinfunction "1_1") (pintype "passive"))
      (node (ref "C28") (pin "1") (pinfunction "1_1") (pintype "passive"))
      (node (ref "GND") (pin "5") (pinfunction "P$5_5") (pintype "bidirectional"))
      (node (ref "IC4") (pin "4") (pinfunction "V+_4") (pintype "power_in"))
      (node (ref "LED1") (pin "A") (pinfunction "A_A") (pintype "passive"))
      (node (ref "R23") (pin "1") (pinfunction "1_1") (pintype "passive"))
      (node (ref "SJ3") (pin "2") (pinfunction "2_2") (pintype "passive"))
      (node (ref "TP20") (pin "TP") (pinfunction "TP_TP") (pintype "input"))
      (node (ref "TP_3.3") (pin "TP") (pinfunction "TP_TP") (pintype "input"))
      (node (ref "U$4") (pin "2") (pinfunction "P$2_2") (pintype "bidirectional"))
      (node (ref "U$4") (pin "3") (pinfunction "P$3_3") (pintype "bidirectional"))
      (node (ref "U$5") (pin "3") (pinfunction "+VDD_3") (pintype "bidirectional"))
      (node (ref "U$5") (pin "7") (pinfunction "DIS_7") (pintype "bidirectional"))
      (node (ref "U1") (pin "5") (pinfunction "V+_5") (pintype "power_in"))
    )
    (net (code "8") (name "/+3.3VJ") (class "Default")
      (node (ref "C35") (pin "2") (pinfunction "2_2") (pintype "passive"))
      (node (ref "C36") (pin "2") (pinfunction "2_2") (pintype "passive"))
      (node (ref "JP9") (pin "2") (pinfunction "2_2") (pintype "passive"))
      (node (ref "R9") (pin "2") (pinfunction "2_2") (pintype "passive"))
      (node (ref "SJ3") (pin "1") (pinfunction "1_1") (pintype "passive"))
      (node (ref "U$3") (pin "19") (pinfunction "VREFB_19") (pintype "bidirectional"))
    )
    (net (code "9") (name "/+5V") (class "Default")
      (node (ref "C1") (pin "1") (pinfunction "1_1") (pintype "passive"))
      (node (ref "C14") (pin "1") (pinfunction "1_1") (pintype "passive"))
      (node (ref "D1") (pin "3") (pinfunction "VIN_3") (pintype "bidirectional"))
      (node (ref "GND") (pin "1") (pinfunction "P$1_1") (pintype "bidirectional"))
      (node (ref "GND") (pin "10") (pinfunction "P$10_10") (pintype "bidirectional"))
      (node (ref "GND") (pin "15") (pinfunction "P$15_15") (pintype "bidirectional"))
      (node (ref "GND") (pin "16") (pinfunction "P$16_16") (pintype "bidirectional"))
      (node (ref "GND") (pin "2") (pinfunction "P$2_2") (pintype "bidirectional"))
      (node (ref "GND") (pin "3") (pinfunction "P$3_3") (pintype "bidirectional"))
      (node (ref "TP16") (pin "TP") (pinfunction "TP_TP") (pintype "input"))
      (node (ref "X7") (pin "VBUS") (pinfunction "VBUS_VBUS") (pintype "bidirectional"))
    )
    (net (code "10") (name "/+VREF_EXT_ADC") (class "Default")
      (node (ref "JP13") (pin "6") (pinfunction "6_6") (pintype "passive"))
      (node (ref "JP28") (pin "1") (pinfunction "1_1") (pintype "passive"))
      (node (ref "TP11") (pin "TP") (pinfunction "TP_TP") (pintype "input"))
    )
    (net (code "11") (name "/+VREF_EXT_DAC") (class "Default")
      (node (ref "JP15") (pin "6") (pinfunction "6_6") (pintype "passive"))
      (node (ref "JP28") (pin "2") (pinfunction "2_2") (pintype "passive"))
      (node (ref "TP21") (pin "TP") (pinfunction "TP_TP") (pintype "input"))
    )
    (net (code "12") (name "/ADC_AXI_CLK") (class "Default")
      (node (ref "JP4") (pin "1") (pinfunction "1_1") (pintype "passive"))
      (node (ref "JP4") (pin "3") (pinfunction "3_3") (pintype "passive"))
      (node (ref "U$1") (pin "ADC_AXI_CLK") (pinfunction "ADC_AXI_CLK_ADC_AXI_CLK") (pintype "bidirectional"))
    )
    (net (code "13") (name "/ADC_AXI_CLK_EXT") (class "Default")
      (node (ref "JP4") (pin "2") (pinfunction "2_2") (pintype "passive"))
      (node (ref "TP13") (pin "TP") (pinfunction "TP_TP") (pintype "input"))
      (node (ref "X2") (pin "1") (pinfunction "1_1") (pintype "passive"))
    )
    (net (code "14") (name "/ADC_AXI_CLK_PLL") (class "Default")
      (node (ref "JP4") (pin "4") (pinfunction "4_4") (pintype "passive"))
      (node (ref "U$4") (pin "8") (pinfunction "P$8_8") (pintype "bidirectional"))
    )
    (net (code "15") (name "/ADC_AXI_N") (class "Default")
      (node (ref "C23") (pin "2") (pinfunction "2_2") (pintype "passive"))
      (node (ref "R25") (pin "2") (pinfunction "2_2") (pintype "passive"))
      (node (ref "U$1") (pin "ADC_AXI_IN") (pinfunction "ADC_AXI_IN_ADC_AXI_IN") (pintype "bidirectional"))
      (node (ref "U$5") (pin "5") (pinfunction "OUT-_5") (pintype "bidirectional"))
    )
    (net (code "16") (name "/ADC_AXI_P") (class "Default")
      (node (ref "C22") (pin "2") (pinfunction "2_2") (pintype "passive"))
      (node (ref "R26") (pin "2") (pinfunction "2_2") (pintype "passive"))
      (node (ref "U$1") (pin "ADC_AXI_IP") (pinfunction "ADC_AXI_IP_ADC_AXI_IP") (pintype "bidirectional"))
      (node (ref "U$5") (pin "4") (pinfunction "OUT+_4") (pintype "bidirectional"))
    )
    (net (code "17") (name "/ADC_AXI_RST") (class "Default")
      (node (ref "JP11") (pin "1") (pinfunction "1_1") (pintype "passive"))
      (node (ref "JP11") (pin "3") (pinfunction "3_3") (pintype "passive"))
      (node (ref "U$1") (pin "ADC_AXI_RST") (pinfunction "ADC_AXI_RST_ADC_AXI_RST") (pintype "bidirectional"))
    )
    (net (code "18") (name "/ADC_AXI_RST_EXT") (class "Default")
      (node (ref "JP11") (pin "2") (pinfunction "2_2") (pintype "passive"))
      (node (ref "TP23") (pin "TP") (pinfunction "TP_TP") (pintype "input"))
      (node (ref "X3") (pin "1") (pinfunction "1_1") (pintype "passive"))
    )
    (net (code "19") (name "/ADC_AXI_RST_PLL") (class "Default")
      (node (ref "JP11") (pin "4") (pinfunction "4_4") (pintype "passive"))
      (node (ref "U$4") (pin "9") (pinfunction "P$9_9") (pintype "bidirectional"))
    )
    (net (code "20") (name "/AXI_CLK") (class "Default")
      (node (ref "JP17") (pin "1") (pinfunction "1_1") (pintype "passive"))
      (node (ref "JP17") (pin "3") (pinfunction "3_3") (pintype "passive"))
      (node (ref "U$1") (pin "AXI_CLK") (pinfunction "AXI_CLK_AXI_CLK") (pintype "bidirectional"))
    )
    (net (code "21") (name "/AXI_CLK_EXT") (class "Default")
      (node (ref "JP17") (pin "2") (pinfunction "2_2") (pintype "passive"))
      (node (ref "TP12") (pin "TP") (pinfunction "TP_TP") (pintype "input"))
      (node (ref "X1") (pin "1") (pinfunction "1_1") (pintype "passive"))
    )
    (net (code "22") (name "/AXI_CLK_PLL") (class "Default")
      (node (ref "JP17") (pin "4") (pinfunction "4_4") (pintype "passive"))
      (node (ref "U$4") (pin "7") (pinfunction "P$7_7") (pintype "bidirectional"))
    )
    (net (code "23") (name "/AXI_RST") (class "Default")
      (node (ref "C13") (pin "2") (pinfunction "2_2") (pintype "passive"))
      (node (ref "R8") (pin "1") (pinfunction "1_1") (pintype "passive"))
      (node (ref "S3") (pin "3") (pinfunction "2.1_3") (pintype "passive"))
      (node (ref "S3") (pin "4") (pinfunction "2.2_4") (pintype "passive"))
      (node (ref "U$1") (pin "AXI_RST") (pinfunction "AXI_RST_AXI_RST") (pintype "bidirectional"))
    )
    (net (code "24") (name "/CEB") (class "Default")
      (node (ref "JP30") (pin "1") (pinfunction "1_1") (pintype "passive"))
      (node (ref "U$3") (pin "12") (pinfunction "B8_12") (pintype "bidirectional"))
    )
    (net (code "25") (name "/CEB_MUX") (class "Default")
      (node (ref "JP1") (pin "3") (pinfunction "3_3") (pintype "passive"))
      (node (ref "JP1") (pin "4") (pinfunction "4_4") (pintype "passive"))
      (node (ref "U$3") (pin "9") (pinfunction "A8_9") (pintype "bidirectional"))
    )
    (net (code "26") (name "/D1") (class "Default")
      (node (ref "JP16") (pin "6") (pinfunction "2_6") (pintype "passive"))
      (node (ref "SG1") (pin "+") (pinfunction "1_+") (pintype "passive"))
    )
    (net (code "27") (name "/DAC_AXI_OUT") (class "Default")
      (node (ref "TP18") (pin "TP") (pinfunction "TP_TP") (pintype "input"))
      (node (ref "U$1") (pin "DAC_AXI_OUT") (pinfunction "DAC_AXI_OUT_DAC_AXI_OUT") (pintype "bidirectional"))
      (node (ref "U1") (pin "1") (pinfunction "IN+_1") (pintype "input"))
    )
    (net (code "28") (name "/DAC_AXI_OUT_BUF") (class "Default")
      (node (ref "JP16") (pin "1") (pinfunction "1_1") (pintype "passive"))
      (node (ref "JP16") (pin "3") (pinfunction "1_3") (pintype "passive"))
      (node (ref "JP16") (pin "5") (pinfunction "1_5") (pintype "passive"))
      (node (ref "JP5") (pin "2") (pinfunction "2_2") (pintype "passive"))
      (node (ref "R21") (pin "1") (pinfunction "1_1") (pintype "passive"))
      (node (ref "TP22") (pin "TP") (pinfunction "TP_TP") (pintype "input"))
      (node (ref "U1") (pin "4") (pinfunction "OUT_4") (pintype "output"))
    )
    (net (code "29") (name "/H_CEB") (class "Default")
      (node (ref "JP1") (pin "2") (pinfunction "2_2") (pintype "passive"))
      (node (ref "R3") (pin "1") (pinfunction "1_1") (pintype "passive"))
      (node (ref "U$1") (pin "H_CEB") (pinfunction "H_CEB_H_CEB") (pintype "bidirectional"))
    )
    (net (code "30") (name "/H_CLK_10") (class "Default")
      (node (ref "U$1") (pin "H_CLK_10") (pinfunction "H_CLK_10_H_CLK_10") (pintype "bidirectional"))
      (node (ref "X4") (pin "1") (pinfunction "1_1") (pintype "passive"))
    )
    (net (code "31") (name "/H_CLK_200") (class "Default")
      (node (ref "U$1") (pin "H_CLK_200") (pinfunction "H_CLK_200_H_CLK_200") (pintype "bidirectional"))
      (node (ref "X5") (pin "1") (pinfunction "1_1") (pintype "passive"))
    )
    (net (code "32") (name "/H_RST") (class "Default")
      (node (ref "C33") (pin "2") (pinfunction "2_2") (pintype "passive"))
      (node (ref "R5") (pin "1") (pinfunction "1_1") (pintype "passive"))
      (node (ref "S4") (pin "3") (pinfunction "2.1_3") (pintype "passive"))
      (node (ref "S4") (pin "4") (pinfunction "2.2_4") (pintype "passive"))
      (node (ref "U$1") (pin "H_RST") (pinfunction "H_RST_H_RST") (pintype "bidirectional"))
    )
    (net (code "33") (name "/I2CSCLK") (class "Default")
      (node (ref "JP7") (pin "2") (pinfunction "2_2") (pintype "passive"))
      (node (ref "U$4") (pin "10") (pinfunction "P$10_10") (pintype "bidirectional"))
    )
    (net (code "34") (name "/I2CSIN") (class "Default")
      (node (ref "JP7") (pin "3") (pinfunction "3_3") (pintype "passive"))
      (node (ref "U$4") (pin "4") (pinfunction "P$4_4") (pintype "bidirectional"))
    )
    (net (code "35") (name "/MISO") (class "Default")
      (node (ref "JP2") (pin "2") (pinfunction "2_2") (pintype "passive"))
      (node (ref "U$3") (pin "15") (pinfunction "B5_15") (pintype "bidirectional"))
    )
    (net (code "36") (name "/MOSI") (class "Default")
      (node (ref "JP2") (pin "4") (pinfunction "4_4") (pintype "passive"))
      (node (ref "U$3") (pin "13") (pinfunction "B7_13") (pintype "bidirectional"))
    )
    (net (code "37") (name "/N$26") (class "Default")
      (node (ref "J1") (pin "2") (pinfunction "LEFT_2") (pintype "bidirectional"))
      (node (ref "J1") (pin "3") (pinfunction "RIGHT_3") (pintype "bidirectional"))
      (node (ref "JP16") (pin "4") (pinfunction "2_4") (pintype "passive"))
    )
    (net (code "38") (name "/P1.1") (class "Default")
      (node (ref "JP3") (pin "1") (pinfunction "1_1") (pintype "passive"))
      (node (ref "JP6") (pin "8") (pinfunction "8_8") (pintype "passive"))
      (node (ref "TP1") (pin "TP") (pinfunction "TP_TP") (pintype "input"))
      (node (ref "U$1") (pin "GPIO00_PAD") (pinfunction "GPIO00_PAD_GPIO00_PAD") (pintype "bidirectional"))
    )
    (net (code "39") (name "/P1.2") (class "Default")
      (node (ref "JP3") (pin "3") (pinfunction "1_3") (pintype "passive"))
      (node (ref "JP6") (pin "7") (pinfunction "7_7") (pintype "passive"))
      (node (ref "TP2") (pin "TP") (pinfunction "TP_TP") (pintype "input"))
      (node (ref "U$1") (pin "GPIO01_PAD") (pinfunction "GPIO01_PAD_GPIO01_PAD") (pintype "bidirectional"))
    )
    (net (code "40") (name "/P1.3") (class "Default")
      (node (ref "JP3") (pin "5") (pinfunction "1_5") (pintype "passive"))
      (node (ref "JP6") (pin "6") (pinfunction "6_6") (pintype "passive"))
      (node (ref "TP3") (pin "TP") (pinfunction "TP_TP") (pintype "input"))
      (node (ref "U$1") (pin "GPIO02_PAD") (pinfunction "GPIO02_PAD_GPIO02_PAD") (pintype "bidirectional"))
    )
    (net (code "41") (name "/P1.4") (class "Default")
      (node (ref "JP3") (pin "7") (pinfunction "1_7") (pintype "passive"))
      (node (ref "JP6") (pin "5") (pinfunction "5_5") (pintype "passive"))
      (node (ref "TP4") (pin "TP") (pinfunction "TP_TP") (pintype "input"))
      (node (ref "U$1") (pin "GPIO03_PAD") (pinfunction "GPIO03_PAD_GPIO03_PAD") (pintype "bidirectional"))
    )
    (net (code "42") (name "/P1.5") (class "Default")
      (node (ref "JP3") (pin "9") (pinfunction "1_9") (pintype "passive"))
      (node (ref "JP6") (pin "4") (pinfunction "4_4") (pintype "passive"))
      (node (ref "TP5") (pin "TP") (pinfunction "TP_TP") (pintype "input"))
      (node (ref "U$1") (pin "GPIO04_PAD") (pinfunction "GPIO04_PAD_GPIO04_PAD") (pintype "bidirectional"))
    )
    (net (code "43") (name "/P1.6") (class "Default")
      (node (ref "JP3") (pin "11") (pinfunction "1_11") (pintype "passive"))
      (node (ref "JP6") (pin "3") (pinfunction "3_3") (pintype "passive"))
      (node (ref "TP6") (pin "TP") (pinfunction "TP_TP") (pintype "input"))
      (node (ref "U$1") (pin "GPIO05_PAD") (pinfunction "GPIO05_PAD_GPIO05_PAD") (pintype "bidirectional"))
    )
    (net (code "44") (name "/P1.7") (class "Default")
      (node (ref "JP6") (pin "2") (pinfunction "2_2") (pintype "passive"))
      (node (ref "JP8") (pin "1") (pinfunction "1_1") (pintype "passive"))
      (node (ref "TP7") (pin "TP") (pinfunction "TP_TP") (pintype "input"))
      (node (ref "U$1") (pin "GPIO06_PAD") (pinfunction "GPIO06_PAD_GPIO06_PAD") (pintype "bidirectional"))
    )
    (net (code "45") (name "/P1.8") (class "Default")
      (node (ref "JP6") (pin "1") (pinfunction "1_1") (pintype "passive"))
      (node (ref "JP8") (pin "3") (pinfunction "1_3") (pintype "passive"))
      (node (ref "TP8") (pin "TP") (pinfunction "TP_TP") (pintype "input"))
      (node (ref "U$1") (pin "GPIO07_PAD") (pinfunction "GPIO07_PAD_GPIO07_PAD") (pintype "bidirectional"))
    )
    (net (code "46") (name "/S.SPI_CEB") (class "Default")
      (node (ref "U$1") (pin "SPI_AXI_SLAVE_CEB") (pinfunction "SPI_AXI_SLAVE_CEB_SPI_AXI_SLAVE_CEB") (pintype "bidirectional"))
      (node (ref "U$3") (pin "5") (pinfunction "A4_5") (pintype "bidirectional"))
    )
    (net (code "47") (name "/S.SPI_DATA") (class "Default")
      (node (ref "U$1") (pin "SPI_AXI_SLAVE_DATA") (pinfunction "SPI_AXI_SLAVE_DATA_SPI_AXI_SLAVE_DATA") (pintype "bidirectional"))
      (node (ref "U$3") (pin "4") (pinfunction "A3_4") (pintype "bidirectional"))
    )
    (net (code "48") (name "/S.SPI_SCLK") (class "Default")
      (node (ref "U$1") (pin "SPI_AXI_SLAVE_SCLK") (pinfunction "SPI_AXI_SLAVE_SCLK_SPI_AXI_SLAVE_SCLK") (pintype "bidirectional"))
      (node (ref "U$3") (pin "3") (pinfunction "A2_3") (pintype "bidirectional"))
    )
    (net (code "49") (name "/SCLK") (class "Default")
      (node (ref "JP2") (pin "3") (pinfunction "3_3") (pintype "passive"))
      (node (ref "U$3") (pin "14") (pinfunction "B6_14") (pintype "bidirectional"))
    )
    (net (code "50") (name "/SLAVE_CEB") (class "Default")
      (node (ref "JP9") (pin "5") (pinfunction "5_5") (pintype "passive"))
      (node (ref "U$3") (pin "16") (pinfunction "B4_16") (pintype "bidirectional"))
    )
    (net (code "51") (name "/SLAVE_DOUT") (class "Default")
      (node (ref "JP9") (pin "4") (pinfunction "4_4") (pintype "passive"))
      (node (ref "U$3") (pin "17") (pinfunction "B3_17") (pintype "bidirectional"))
    )
    (net (code "52") (name "/SLAVE_SCLK") (class "Default")
      (node (ref "JP9") (pin "3") (pinfunction "3_3") (pintype "passive"))
      (node (ref "U$3") (pin "18") (pinfunction "B2_18") (pintype "bidirectional"))
    )
    (net (code "53") (name "/SPI_AXI_MASTER_CEB") (class "Default")
      (node (ref "JP1") (pin "1") (pinfunction "1_1") (pintype "passive"))
      (node (ref "R4") (pin "1") (pinfunction "1_1") (pintype "passive"))
      (node (ref "U$1") (pin "SPI_AXI_MASTER_CEB") (pinfunction "SPI_AXI_MASTER_CEB_SPI_AXI_MASTER_CEB") (pintype "bidirectional"))
    )
    (net (code "54") (name "/SPI_CLK") (class "Default")
      (node (ref "U$1") (pin "H_CLK") (pinfunction "H_CLK_H_CLK") (pintype "bidirectional"))
      (node (ref "U$1") (pin "SPI_AXI_MASTER_SCLK") (pinfunction "SPI_AXI_MASTER_SCLK_SPI_AXI_MASTER_SCLK") (pintype "bidirectional"))
      (node (ref "U$3") (pin "7") (pinfunction "A6_7") (pintype "bidirectional"))
    )
    (net (code "55") (name "/SPI_DATA") (class "Default")
      (node (ref "U$1") (pin "H_DATA") (pinfunction "H_DATA_H_DATA") (pintype "bidirectional"))
      (node (ref "U$1") (pin "SPI_AXI_MASTER_DATA") (pinfunction "SPI_AXI_MASTER_DATA_SPI_AXI_MASTER_DATA") (pintype "bidirectional"))
      (node (ref "U$3") (pin "8") (pinfunction "A7_8") (pintype "bidirectional"))
    )
    (net (code "56") (name "/SPI_DOUT") (class "Default")
      (node (ref "U$1") (pin "H_DOUT") (pinfunction "H_DOUT_H_DOUT") (pintype "bidirectional"))
      (node (ref "U$1") (pin "SPI_AXI_MASTER_DOUT") (pinfunction "SPI_AXI_MASTER_DOUT_SPI_AXI_MASTER_DOUT") (pintype "bidirectional"))
      (node (ref "U$3") (pin "6") (pinfunction "A5_6") (pintype "bidirectional"))
    )
    (net (code "57") (name "/VDDPOC") (class "Default")
      (node (ref "JP12") (pin "2") (pinfunction "2_2") (pintype "passive"))
      (node (ref "SJ4") (pin "2") (pinfunction "2_2") (pintype "passive"))
      (node (ref "TP19") (pin "TP") (pinfunction "TP_TP") (pintype "input"))
      (node (ref "U$1") (pin "VDDPOC") (pinfunction "VDDPOC_VDDPOC") (pintype "bidirectional"))
    )
    (net (code "58") (name "ADC_AXI_N_EXT") (class "Default")
      (node (ref "IC4") (pin "12") (pinfunction "IN+_12") (pintype "input"))
      (node (ref "JP14") (pin "2") (pinfunction "2_2") (pintype "passive"))
      (node (ref "TP10") (pin "TP") (pinfunction "TP_TP") (pintype "input"))
    )
    (net (code "59") (name "ADC_AXI_P_EXT") (class "Default")
      (node (ref "IC4") (pin "3") (pinfunction "IN+_3") (pintype "input"))
      (node (ref "JP14") (pin "3") (pinfunction "3_3") (pintype "passive"))
      (node (ref "TP9") (pin "TP") (pinfunction "TP_TP") (pintype "input"))
    )
    (net (code "60") (name "GND") (class "Default")
      (node (ref "C1") (pin "2") (pinfunction "2_2") (pintype "passive"))
      (node (ref "C10") (pin "1") (pinfunction "1_1") (pintype "passive"))
      (node (ref "C11") (pin "1") (pinfunction "1_1") (pintype "passive"))
      (node (ref "C12") (pin "1") (pinfunction "1_1") (pintype "passive"))
      (node (ref "C13") (pin "1") (pinfunction "1_1") (pintype "passive"))
      (node (ref "C14") (pin "2") (pinfunction "2_2") (pintype "passive"))
      (node (ref "C15") (pin "2") (pinfunction "2_2") (pintype "passive"))
      (node (ref "C16") (pin "2") (pinfunction "2_2") (pintype "passive"))
      (node (ref "C17") (pin "2") (pinfunction "2_2") (pintype "passive"))
      (node (ref "C18") (pin "1") (pinfunction "1_1") (pintype "passive"))
      (node (ref "C19") (pin "2") (pinfunction "2_2") (pintype "passive"))
      (node (ref "C2") (pin "2") (pinfunction "2_2") (pintype "passive"))
      (node (ref "C20") (pin "2") (pinfunction "2_2") (pintype "passive"))
      (node (ref "C21") (pin "2") (pinfunction "2_2") (pintype "passive"))
      (node (ref "C24") (pin "1") (pinfunction "1_1") (pintype "passive"))
      (node (ref "C25") (pin "2") (pinfunction "2_2") (pintype "passive"))
      (node (ref "C26") (pin "2") (pinfunction "2_2") (pintype "passive"))
      (node (ref "C27") (pin "2") (pinfunction "2_2") (pintype "passive"))
      (node (ref "C28") (pin "2") (pinfunction "2_2") (pintype "passive"))
      (node (ref "C29") (pin "2") (pinfunction "2_2") (pintype "passive"))
      (node (ref "C3") (pin "2") (pinfunction "2_2") (pintype "passive"))
      (node (ref "C30") (pin "2") (pinfunction "2_2") (pintype "passive"))
      (node (ref "C31") (pin "1") (pinfunction "1_1") (pintype "passive"))
      (node (ref "C32") (pin "1") (pinfunction "1_1") (pintype "passive"))
      (node (ref "C33") (pin "1") (pinfunction "1_1") (pintype "passive"))
      (node (ref "C34") (pin "1") (pinfunction "1_1") (pintype "passive"))
      (node (ref "C35") (pin "1") (pinfunction "1_1") (pintype "passive"))
      (node (ref "C36") (pin "1") (pinfunction "1_1") (pintype "passive"))
      (node (ref "C37") (pin "1") (pinfunction "1_1") (pintype "passive"))
      (node (ref "C38") (pin "1") (pinfunction "1_1") (pintype "passive"))
      (node (ref "C39") (pin "2") (pinfunction "2_2") (pintype "passive"))
      (node (ref "C4") (pin "2") (pinfunction "2_2") (pintype "passive"))
      (node (ref "C40") (pin "2") (pinfunction "2_2") (pintype "passive"))
      (node (ref "C41") (pin "2") (pinfunction "2_2") (pintype "passive"))
      (node (ref "C5") (pin "2") (pinfunction "2_2") (pintype "passive"))
      (node (ref "C6") (pin "2") (pinfunction "2_2") (pintype "passive"))
      (node (ref "C7") (pin "2") (pinfunction "2_2") (pintype "passive"))
      (node (ref "C8") (pin "2") (pinfunction "2_2") (pintype "passive"))
      (node (ref "C9") (pin "1") (pinfunction "1_1") (pintype "passive"))
      (node (ref "D1") (pin "1") (pinfunction "GND_1") (pintype "bidirectional"))
      (node (ref "GND") (pin "12") (pinfunction "P$12_12") (pintype "bidirectional"))
      (node (ref "GND") (pin "EXP") (pinfunction "P$17_EXP") (pintype "bidirectional"))
      (node (ref "IC2") (pin "2") (pinfunction "VO_2") (pintype "input"))
      (node (ref "IC2") (pin "3") (pinfunction "GND_3") (pintype "power_in"))
      (node (ref "IC4") (pin "11") (pinfunction "V-_11") (pintype "power_in"))
      (node (ref "J1") (pin "1") (pinfunction "SLEEVE_1") (pintype "bidirectional"))
      (node (ref "JP10") (pin "1") (pinfunction "1_1") (pintype "passive"))
      (node (ref "JP12") (pin "1") (pinfunction "1_1") (pintype "passive"))
      (node (ref "JP14") (pin "1") (pinfunction "1_1") (pintype "passive"))
      (node (ref "JP18") (pin "1") (pinfunction "1_1") (pintype "passive"))
      (node (ref "JP19") (pin "1") (pinfunction "1_1") (pintype "passive"))
      (node (ref "JP2") (pin "1") (pinfunction "1_1") (pintype "passive"))
      (node (ref "JP20") (pin "1") (pinfunction "1_1") (pintype "passive"))
      (node (ref "JP21") (pin "1") (pinfunction "1_1") (pintype "passive"))
      (node (ref "JP22") (pin "1") (pinfunction "1_1") (pintype "passive"))
      (node (ref "JP23") (pin "1") (pinfunction "1_1") (pintype "passive"))
      (node (ref "JP24") (pin "1") (pinfunction "1_1") (pintype "passive"))
      (node (ref "JP25") (pin "1") (pinfunction "1_1") (pintype "passive"))
      (node (ref "JP26") (pin "1") (pinfunction "1_1") (pintype "passive"))
      (node (ref "JP27") (pin "1") (pinfunction "1_1") (pintype "passive"))
      (node (ref "JP29") (pin "1") (pinfunction "1_1") (pintype "passive"))
      (node (ref "JP5") (pin "1") (pinfunction "1_1") (pintype "passive"))
      (node (ref "JP7") (pin "1") (pinfunction "1_1") (pintype "passive"))
      (node (ref "JP9") (pin "1") (pinfunction "1_1") (pintype "passive"))
      (node (ref "R1") (pin "1") (pinfunction "1_1") (pintype "passive"))
      (node (ref "R11") (pin "1") (pinfunction "1_1") (pintype "passive"))
      (node (ref "R12") (pin "1") (pinfunction "1_1") (pintype "passive"))
      (node (ref "R13") (pin "1") (pinfunction "1_1") (pintype "passive"))
      (node (ref "R14") (pin "1") (pinfunction "1_1") (pintype "passive"))
      (node (ref "R15") (pin "1") (pinfunction "1_1") (pintype "passive"))
      (node (ref "R19") (pin "1") (pinfunction "1_1") (pintype "passive"))
      (node (ref "R2") (pin "1") (pinfunction "1_1") (pintype "passive"))
      (node (ref "R20") (pin "1") (pinfunction "1_1") (pintype "passive"))
      (node (ref "R22") (pin "2") (pinfunction "2_2") (pintype "passive"))
      (node (ref "R27") (pin "1") (pinfunction "A_1") (pintype "passive"))
      (node (ref "R28") (pin "1") (pinfunction "1_1") (pintype "passive"))
      (node (ref "R32") (pin "2") (pinfunction "2_2") (pintype "passive"))
      (node (ref "R6") (pin "1") (pinfunction "A_1") (pintype "passive"))
      (node (ref "R7") (pin "1") (pinfunction "1_1") (pintype "passive"))
      (node (ref "S1") (pin "3") (pinfunction "2.1_3") (pintype "passive"))
      (node (ref "S1") (pin "4") (pinfunction "2.2_4") (pintype "passive"))
      (node (ref "S2") (pin "3") (pinfunction "2.1_3") (pintype "passive"))
      (node (ref "S2") (pin "4") (pinfunction "2.2_4") (pintype "passive"))
      (node (ref "S3") (pin "1") (pinfunction "1.1_1") (pintype "passive"))
      (node (ref "S3") (pin "2") (pinfunction "1.2_2") (pintype "passive"))
      (node (ref "S4") (pin "1") (pinfunction "1.1_1") (pintype "passive"))
      (node (ref "S4") (pin "2") (pinfunction "1.2_2") (pintype "passive"))
      (node (ref "SG1") (pin "-") (pinfunction "2_-") (pintype "passive"))
      (node (ref "TP40") (pin "TP") (pinfunction "TP_TP") (pintype "input"))
      (node (ref "TP41") (pin "TP") (pinfunction "TP_TP") (pintype "input"))
      (node (ref "TP42") (pin "TP") (pinfunction "TP_TP") (pintype "input"))
      (node (ref "U$1") (pin "AVSS@1") (pinfunction "AVSS_AVSS@1") (pintype "bidirectional"))
      (node (ref "U$1") (pin "AVSS@2") (pinfunction "AVSS_AVSS@2") (pintype "bidirectional"))
      (node (ref "U$1") (pin "AVSS@3") (pinfunction "AVSS_AVSS@3") (pintype "bidirectional"))
      (node (ref "U$1") (pin "AVSS@4") (pinfunction "AVSS_AVSS@4") (pintype "bidirectional"))
      (node (ref "U$1") (pin "N$10000") (pinfunction "VSSPST_N$10000") (pintype "bidirectional"))
      (node (ref "U$1") (pin "VSS@1") (pinfunction "VSS_VSS@1") (pintype "bidirectional"))
      (node (ref "U$1") (pin "VSS@2") (pinfunction "VSS_VSS@2") (pintype "bidirectional"))
      (node (ref "U$1") (pin "VSS@3") (pinfunction "VSS_VSS@3") (pintype "bidirectional"))
      (node (ref "U$1") (pin "VSS@4") (pinfunction "VSS_VSS@4") (pintype "bidirectional"))
      (node (ref "U$1") (pin "VSS@5") (pinfunction "VSS_VSS@5") (pintype "bidirectional"))
      (node (ref "U$1") (pin "VSS@6") (pinfunction "VSS_VSS@6") (pintype "bidirectional"))
      (node (ref "U$1") (pin "VSS@7") (pinfunction "VSS_VSS@7") (pintype "bidirectional"))
      (node (ref "U$1") (pin "VSS@8") (pinfunction "VSS_VSS@8") (pintype "bidirectional"))
      (node (ref "U$1") (pin "VSSPST@2") (pinfunction "VSSPST_VSSPST@2") (pintype "bidirectional"))
      (node (ref "U$3") (pin "11") (pinfunction "GND_11") (pintype "bidirectional"))
      (node (ref "U$4") (pin "13") (pinfunction "P$13_13") (pintype "bidirectional"))
      (node (ref "U$4") (pin "5") (pinfunction "P$5_5") (pintype "bidirectional"))
      (node (ref "U$4") (pin "6") (pinfunction "P$6_6") (pintype "bidirectional"))
      (node (ref "U$5") (pin "6") (pinfunction "-VSS_6") (pintype "bidirectional"))
      (node (ref "U1") (pin "2") (pinfunction "V-_2") (pintype "power_in"))
      (node (ref "U2") (pin "2") (pinfunction "GND_2") (pintype "bidirectional"))
      (node (ref "U2") (pin "4") (pinfunction "GND1_4") (pintype "bidirectional"))
      (node (ref "X1") (pin "2") (pinfunction "2_2") (pintype "passive"))
      (node (ref "X1") (pin "3") (pinfunction "2_3") (pintype "passive"))
      (node (ref "X1") (pin "4") (pinfunction "2_4") (pintype "passive"))
      (node (ref "X1") (pin "5") (pinfunction "2_5") (pintype "passive"))
      (node (ref "X2") (pin "2") (pinfunction "2_2") (pintype "passive"))
      (node (ref "X2") (pin "3") (pinfunction "2_3") (pintype "passive"))
      (node (ref "X2") (pin "4") (pinfunction "2_4") (pintype "passive"))
      (node (ref "X2") (pin "5") (pinfunction "2_5") (pintype "passive"))
      (node (ref "X3") (pin "2") (pinfunction "2_2") (pintype "passive"))
      (node (ref "X3") (pin "3") (pinfunction "2_3") (pintype "passive"))
      (node (ref "X3") (pin "4") (pinfunction "2_4") (pintype "passive"))
      (node (ref "X3") (pin "5") (pinfunction "2_5") (pintype "passive"))
      (node (ref "X4") (pin "2") (pinfunction "2_2") (pintype "passive"))
      (node (ref "X4") (pin "3") (pinfunction "2_3") (pintype "passive"))
      (node (ref "X4") (pin "4") (pinfunction "2_4") (pintype "passive"))
      (node (ref "X4") (pin "5") (pinfunction "2_5") (pintype "passive"))
      (node (ref "X5") (pin "2") (pinfunction "2_2") (pintype "passive"))
      (node (ref "X5") (pin "3") (pinfunction "2_3") (pintype "passive"))
      (node (ref "X5") (pin "4") (pinfunction "2_4") (pintype "passive"))
      (node (ref "X5") (pin "5") (pinfunction "2_5") (pintype "passive"))
      (node (ref "X7") (pin "GND") (pinfunction "GND_GND") (pintype "bidirectional"))
      (node (ref "X7") (pin "P$5") (pinfunction "GND1_P$5") (pintype "bidirectional"))
      (node (ref "X7") (pin "P$6") (pinfunction "GND2_P$6") (pintype "bidirectional"))
    )
    (net (code "61") (name "Net-(C10-Pad2)") (class "Default")
      (node (ref "C10") (pin "2") (pinfunction "2_2") (pintype "passive"))
      (node (ref "C11") (pin "2") (pinfunction "2_2") (pintype "passive"))
      (node (ref "C12") (pin "2") (pinfunction "2_2") (pintype "passive"))
      (node (ref "SJ1") (pin "2") (pinfunction "2_2") (pintype "passive"))
      (node (ref "TP43") (pin "TP") (pinfunction "TP_TP") (pintype "input"))
      (node (ref "U$1") (pin "AVDD@1") (pinfunction "AVDD_AVDD@1") (pintype "bidirectional"))
      (node (ref "U$1") (pin "AVDD@2") (pinfunction "AVDD_AVDD@2") (pintype "bidirectional"))
    )
    (net (code "62") (name "Net-(IC4A-IN-)") (class "Default")
      (node (ref "IC4") (pin "1") (pinfunction "OUT_1") (pintype "output"))
      (node (ref "IC4") (pin "2") (pinfunction "IN-_2") (pintype "input"))
      (node (ref "R18") (pin "1") (pinfunction "1_1") (pintype "passive"))
    )
    (net (code "63") (name "Net-(IC4B-IN+)") (class "Default")
      (node (ref "IC4") (pin "5") (pinfunction "IN+_5") (pintype "input"))
      (node (ref "JP13") (pin "1") (pinfunction "1_1") (pintype "passive"))
      (node (ref "JP13") (pin "3") (pinfunction "3_3") (pintype "passive"))
      (node (ref "JP13") (pin "5") (pinfunction "5_5") (pintype "passive"))
    )
    (net (code "64") (name "Net-(IC4C-IN+)") (class "Default")
      (node (ref "IC4") (pin "10") (pinfunction "IN+_10") (pintype "input"))
      (node (ref "JP15") (pin "1") (pinfunction "1_1") (pintype "passive"))
      (node (ref "JP15") (pin "3") (pinfunction "3_3") (pintype "passive"))
      (node (ref "JP15") (pin "5") (pinfunction "5_5") (pintype "passive"))
    )
    (net (code "65") (name "Net-(IC4D-IN-)") (class "Default")
      (node (ref "IC4") (pin "13") (pinfunction "IN-_13") (pintype "input"))
      (node (ref "IC4") (pin "14") (pinfunction "OUT_14") (pintype "output"))
      (node (ref "R24") (pin "1") (pinfunction "1_1") (pintype "passive"))
    )
    (net (code "66") (name "Net-(JP3-Pad2)") (class "Default")
      (node (ref "JP3") (pin "2") (pinfunction "2_2") (pintype "passive"))
      (node (ref "LED3") (pin "A") (pinfunction "A_A") (pintype "passive"))
    )
    (net (code "67") (name "Net-(JP3B-2)") (class "Default")
      (node (ref "JP3") (pin "4") (pinfunction "2_4") (pintype "passive"))
      (node (ref "LED4") (pin "A") (pinfunction "A_A") (pintype "passive"))
    )
    (net (code "68") (name "Net-(JP3C-2)") (class "Default")
      (node (ref "JP3") (pin "6") (pinfunction "2_6") (pintype "passive"))
      (node (ref "LED5") (pin "A") (pinfunction "A_A") (pintype "passive"))
    )
    (net (code "69") (name "Net-(JP3D-2)") (class "Default")
      (node (ref "JP3") (pin "8") (pinfunction "2_8") (pintype "passive"))
      (node (ref "LED6") (pin "A") (pinfunction "A_A") (pintype "passive"))
    )
    (net (code "70") (name "Net-(JP3E-2)") (class "Default")
      (node (ref "JP3") (pin "10") (pinfunction "2_10") (pintype "passive"))
      (node (ref "LED7") (pin "A") (pinfunction "A_A") (pintype "passive"))
    )
    (net (code "71") (name "Net-(JP3F-2)") (class "Default")
      (node (ref "JP3") (pin "12") (pinfunction "2_12") (pintype "passive"))
      (node (ref "LED8") (pin "A") (pinfunction "A_A") (pintype "passive"))
    )
    (net (code "72") (name "Net-(JP8B-2)") (class "Default")
      (node (ref "C32") (pin "2") (pinfunction "2_2") (pintype "passive"))
      (node (ref "JP8") (pin "4") (pinfunction "2_4") (pintype "passive"))
      (node (ref "R17") (pin "2") (pinfunction "2_2") (pintype "passive"))
      (node (ref "S2") (pin "1") (pinfunction "1.1_1") (pintype "passive"))
      (node (ref "S2") (pin "2") (pinfunction "1.2_2") (pintype "passive"))
    )
    (net (code "73") (name "Net-(JP16-Pad2)") (class "Default")
      (node (ref "JP16") (pin "2") (pinfunction "2_2") (pintype "passive"))
      (node (ref "LED10") (pin "A") (pinfunction "A_A") (pintype "passive"))
    )
    (net (code "74") (name "Net-(LED1-PadC)") (class "Default")
      (node (ref "LED1") (pin "C") (pinfunction "C_C") (pintype "passive"))
      (node (ref "R1") (pin "2") (pinfunction "2_2") (pintype "passive"))
    )
    (net (code "75") (name "Net-(LED2-PadC)") (class "Default")
      (node (ref "LED2") (pin "C") (pinfunction "C_C") (pintype "passive"))
      (node (ref "R2") (pin "2") (pinfunction "2_2") (pintype "passive"))
    )
    (net (code "76") (name "Net-(LED3-PadC)") (class "Default")
      (node (ref "LED3") (pin "C") (pinfunction "C_C") (pintype "passive"))
      (node (ref "R11") (pin "2") (pinfunction "2_2") (pintype "passive"))
    )
    (net (code "77") (name "Net-(LED4-PadC)") (class "Default")
      (node (ref "LED4") (pin "C") (pinfunction "C_C") (pintype "passive"))
      (node (ref "R7") (pin "2") (pinfunction "2_2") (pintype "passive"))
    )
    (net (code "78") (name "Net-(LED5-PadC)") (class "Default")
      (node (ref "LED5") (pin "C") (pinfunction "C_C") (pintype "passive"))
      (node (ref "R12") (pin "2") (pinfunction "2_2") (pintype "passive"))
    )
    (net (code "79") (name "Net-(LED6-PadC)") (class "Default")
      (node (ref "LED6") (pin "C") (pinfunction "C_C") (pintype "passive"))
      (node (ref "R13") (pin "2") (pinfunction "2_2") (pintype "passive"))
    )
    (net (code "80") (name "Net-(LED7-PadC)") (class "Default")
      (node (ref "LED7") (pin "C") (pinfunction "C_C") (pintype "passive"))
      (node (ref "R14") (pin "2") (pinfunction "2_2") (pintype "passive"))
    )
    (net (code "81") (name "Net-(LED8-PadC)") (class "Default")
      (node (ref "LED8") (pin "C") (pinfunction "C_C") (pintype "passive"))
      (node (ref "R15") (pin "2") (pinfunction "2_2") (pintype "passive"))
    )
    (net (code "82") (name "Net-(LED9-PadC)") (class "Default")
      (node (ref "LED9") (pin "C") (pinfunction "C_C") (pintype "passive"))
      (node (ref "R19") (pin "2") (pinfunction "2_2") (pintype "passive"))
    )
    (net (code "83") (name "Net-(LED10-PadC)") (class "Default")
      (node (ref "LED10") (pin "C") (pinfunction "C_C") (pintype "passive"))
      (node (ref "R20") (pin "2") (pinfunction "2_2") (pintype "passive"))
    )
    (net (code "84") (name "Net-(LED11-PadC)") (class "Default")
      (node (ref "LED11") (pin "C") (pinfunction "C_C") (pintype "passive"))
      (node (ref "R28") (pin "2") (pinfunction "2_2") (pintype "passive"))
    )
    (net (code "85") (name "Net-(R6-S)") (class "Default")
      (node (ref "JP13") (pin "4") (pinfunction "4_4") (pintype "passive"))
      (node (ref "R6") (pin "2") (pinfunction "S_2") (pintype "passive"))
    )
    (net (code "86") (name "Net-(R27-S)") (class "Default")
      (node (ref "JP15") (pin "4") (pinfunction "4_4") (pintype "passive"))
      (node (ref "R27") (pin "2") (pinfunction "S_2") (pintype "passive"))
    )
    (net (code "87") (name "Net-(S1-1.1)") (class "Default")
      (node (ref "C31") (pin "2") (pinfunction "2_2") (pintype "passive"))
      (node (ref "JP8") (pin "2") (pinfunction "2_2") (pintype "passive"))
      (node (ref "R16") (pin "2") (pinfunction "2_2") (pintype "passive"))
      (node (ref "S1") (pin "1") (pinfunction "1.1_1") (pintype "passive"))
      (node (ref "S1") (pin "2") (pinfunction "1.2_2") (pintype "passive"))
    )
    (net (code "88") (name "Net-(U$3-EN)") (class "Default")
      (node (ref "C34") (pin "2") (pinfunction "2_2") (pintype "passive"))
      (node (ref "JP10") (pin "2") (pinfunction "2_2") (pintype "passive"))
      (node (ref "R9") (pin "1") (pinfunction "1_1") (pintype "passive"))
      (node (ref "U$3") (pin "10") (pinfunction "EN_10") (pintype "bidirectional"))
    )
    (net (code "89") (name "Net-(U$4-P$1)") (class "Default")
      (node (ref "U$4") (pin "1") (pinfunction "P$1_1") (pintype "bidirectional"))
      (node (ref "U2") (pin "1") (pinfunction "1_1") (pintype "bidirectional"))
    )
    (net (code "90") (name "Net-(U$4-P$16)") (class "Default")
      (node (ref "U$4") (pin "16") (pinfunction "P$16_16") (pintype "bidirectional"))
      (node (ref "U2") (pin "3") (pinfunction "3_3") (pintype "bidirectional"))
    )
    (net (code "91") (name "Net-(U$5-IN+)") (class "Default")
      (node (ref "C23") (pin "1") (pinfunction "1_1") (pintype "passive"))
      (node (ref "R18") (pin "2") (pinfunction "2_2") (pintype "passive"))
      (node (ref "R25") (pin "1") (pinfunction "1_1") (pintype "passive"))
      (node (ref "U$5") (pin "8") (pinfunction "IN+_8") (pintype "bidirectional"))
    )
    (net (code "92") (name "Net-(U$5-IN-)") (class "Default")
      (node (ref "C22") (pin "1") (pinfunction "1_1") (pintype "passive"))
      (node (ref "R24") (pin "2") (pinfunction "2_2") (pintype "passive"))
      (node (ref "R26") (pin "1") (pinfunction "1_1") (pintype "passive"))
      (node (ref "U$5") (pin "1") (pinfunction "IN-_1") (pintype "bidirectional"))
    )
    (net (code "93") (name "Net-(U1-IN-)") (class "Default")
      (node (ref "R21") (pin "2") (pinfunction "2_2") (pintype "passive"))
      (node (ref "R22") (pin "1") (pinfunction "1_1") (pintype "passive"))
      (node (ref "U1") (pin "3") (pinfunction "IN-_3") (pintype "input"))
    )
    (net (code "94") (name "VREF_ADC") (class "Default")
      (node (ref "C40") (pin "1") (pinfunction "1_1") (pintype "passive"))
      (node (ref "IC4") (pin "6") (pinfunction "IN-_6") (pintype "input"))
      (node (ref "IC4") (pin "7") (pinfunction "OUT_7") (pintype "output"))
      (node (ref "R31") (pin "2") (pinfunction "2_2") (pintype "passive"))
      (node (ref "TP39") (pin "TP") (pinfunction "TP_TP") (pintype "input"))
      (node (ref "U$1") (pin "VREF_ADC") (pinfunction "VREF_ADC_VREF_ADC") (pintype "bidirectional"))
    )
    (net (code "95") (name "VREF_DAC") (class "Default")
      (node (ref "C41") (pin "1") (pinfunction "1_1") (pintype "passive"))
      (node (ref "IC4") (pin "8") (pinfunction "OUT_8") (pintype "output"))
      (node (ref "IC4") (pin "9") (pinfunction "IN-_9") (pintype "input"))
      (node (ref "TP17") (pin "TP") (pinfunction "TP_TP") (pintype "input"))
      (node (ref "U$1") (pin "VREF_DAC") (pinfunction "VREF_DAC_VREF_DAC") (pintype "bidirectional"))
    )
    (net (code "96") (name "unconnected-(GND-P$4-Pad4)") (class "Default")
      (node (ref "GND") (pin "4") (pinfunction "P$4_4") (pintype "bidirectional"))
    )
    (net (code "97") (name "unconnected-(GND-P$7-Pad7)") (class "Default")
      (node (ref "GND") (pin "7") (pinfunction "P$7_7") (pintype "bidirectional"))
    )
    (net (code "98") (name "unconnected-(GND-P$9-Pad9)") (class "Default")
      (node (ref "GND") (pin "9") (pinfunction "P$9_9") (pintype "bidirectional"))
    )
    (net (code "99") (name "unconnected-(GND-P$11-Pad11)") (class "Default")
      (node (ref "GND") (pin "11") (pinfunction "P$11_11") (pintype "bidirectional"))
    )
    (net (code "100") (name "unconnected-(GND-P$13-Pad13)") (class "Default")
      (node (ref "GND") (pin "13") (pinfunction "P$13_13") (pintype "bidirectional"))
    )
    (net (code "101") (name "unconnected-(GND-P$14-Pad14)") (class "Default")
      (node (ref "GND") (pin "14") (pinfunction "P$14_14") (pintype "bidirectional"))
    )
    (net (code "102") (name "unconnected-(TP26-PadTP)") (class "Default")
      (node (ref "TP26") (pin "TP") (pinfunction "TP_TP") (pintype "input"))
    )
    (net (code "103") (name "unconnected-(TP27-PadTP)") (class "Default")
      (node (ref "TP27") (pin "TP") (pinfunction "TP_TP") (pintype "input"))
    )
    (net (code "104") (name "unconnected-(TP28-PadTP)") (class "Default")
      (node (ref "TP28") (pin "TP") (pinfunction "TP_TP") (pintype "input"))
    )
    (net (code "105") (name "unconnected-(TP29-PadTP)") (class "Default")
      (node (ref "TP29") (pin "TP") (pinfunction "TP_TP") (pintype "input"))
    )
    (net (code "106") (name "unconnected-(TP30-PadTP)") (class "Default")
      (node (ref "TP30") (pin "TP") (pinfunction "TP_TP") (pintype "input"))
    )
    (net (code "107") (name "unconnected-(TP31-PadTP)") (class "Default")
      (node (ref "TP31") (pin "TP") (pinfunction "TP_TP") (pintype "input"))
    )
    (net (code "108") (name "unconnected-(TP32-PadTP)") (class "Default")
      (node (ref "TP32") (pin "TP") (pinfunction "TP_TP") (pintype "input"))
    )
    (net (code "109") (name "unconnected-(TP33-PadTP)") (class "Default")
      (node (ref "TP33") (pin "TP") (pinfunction "TP_TP") (pintype "input"))
    )
    (net (code "110") (name "unconnected-(TP34-PadTP)") (class "Default")
      (node (ref "TP34") (pin "TP") (pinfunction "TP_TP") (pintype "input"))
    )
    (net (code "111") (name "unconnected-(TP35-PadTP)") (class "Default")
      (node (ref "TP35") (pin "TP") (pinfunction "TP_TP") (pintype "input"))
    )
    (net (code "112") (name "unconnected-(TP36-PadTP)") (class "Default")
      (node (ref "TP36") (pin "TP") (pinfunction "TP_TP") (pintype "input"))
    )
    (net (code "113") (name "unconnected-(TP37-PadTP)") (class "Default")
      (node (ref "TP37") (pin "TP") (pinfunction "TP_TP") (pintype "input"))
    )
    (net (code "114") (name "unconnected-(TP38-PadTP)") (class "Default")
      (node (ref "TP38") (pin "TP") (pinfunction "TP_TP") (pintype "input"))
    )
    (net (code "115") (name "unconnected-(U$3-A1-Pad1)") (class "Default")
      (node (ref "U$3") (pin "1") (pinfunction "A1_1") (pintype "bidirectional"))
    )
    (net (code "116") (name "unconnected-(U$3-B1-Pad20)") (class "Default")
      (node (ref "U$3") (pin "20") (pinfunction "B1_20") (pintype "bidirectional"))
    )
    (net (code "117") (name "unconnected-(U$4-P$12-Pad12)") (class "Default")
      (node (ref "U$4") (pin "12") (pinfunction "P$12_12") (pintype "bidirectional"))
    )
    (net (code "118") (name "unconnected-(U$4-P$14-Pad14)") (class "Default")
      (node (ref "U$4") (pin "14") (pinfunction "P$14_14") (pintype "bidirectional"))
    )
    (net (code "119") (name "unconnected-(U$4-P$15-Pad15)") (class "Default")
      (node (ref "U$4") (pin "15") (pinfunction "P$15_15") (pintype "bidirectional"))
    )
    (net (code "120") (name "unconnected-(U$6-AVDD-PadAVDD@1)") (class "Default")
      (node (ref "U$6") (pin "AVDD@1") (pinfunction "AVDD_AVDD@1") (pintype "bidirectional"))
    )
    (net (code "121") (name "unconnected-(U$6-AVDD-PadAVDD@2)") (class "Default")
      (node (ref "U$6") (pin "AVDD@2") (pinfunction "AVDD_AVDD@2") (pintype "bidirectional"))
    )
    (net (code "122") (name "unconnected-(U$6-AVSS-PadAVSS@1)") (class "Default")
      (node (ref "U$6") (pin "AVSS@1") (pinfunction "AVSS_AVSS@1") (pintype "bidirectional"))
    )
    (net (code "123") (name "unconnected-(U$6-AVSS-PadAVSS@2)") (class "Default")
      (node (ref "U$6") (pin "AVSS@2") (pinfunction "AVSS_AVSS@2") (pintype "bidirectional"))
    )
    (net (code "124") (name "unconnected-(U$6-AVSS-PadAVSS@3)") (class "Default")
      (node (ref "U$6") (pin "AVSS@3") (pinfunction "AVSS_AVSS@3") (pintype "bidirectional"))
    )
    (net (code "125") (name "unconnected-(U$6-AVSS-PadAVSS@4)") (class "Default")
      (node (ref "U$6") (pin "AVSS@4") (pinfunction "AVSS_AVSS@4") (pintype "bidirectional"))
    )
    (net (code "126") (name "unconnected-(U$6-PadADC_AXI_CLK)") (class "Default")
      (node (ref "U$6") (pin "ADC_AXI_CLK") (pinfunction "ADC_AXI_CLK_ADC_AXI_CLK") (pintype "bidirectional"))
    )
    (net (code "127") (name "unconnected-(U$6-PadADC_AXI_IN)") (class "Default")
      (node (ref "U$6") (pin "ADC_AXI_IN") (pinfunction "ADC_AXI_IN_ADC_AXI_IN") (pintype "bidirectional"))
    )
    (net (code "128") (name "unconnected-(U$6-PadADC_AXI_IP)") (class "Default")
      (node (ref "U$6") (pin "ADC_AXI_IP") (pinfunction "ADC_AXI_IP_ADC_AXI_IP") (pintype "bidirectional"))
    )
    (net (code "129") (name "unconnected-(U$6-PadADC_AXI_RST)") (class "Default")
      (node (ref "U$6") (pin "ADC_AXI_RST") (pinfunction "ADC_AXI_RST_ADC_AXI_RST") (pintype "bidirectional"))
    )
    (net (code "130") (name "unconnected-(U$6-PadAXI_CLK)") (class "Default")
      (node (ref "U$6") (pin "AXI_CLK") (pinfunction "AXI_CLK_AXI_CLK") (pintype "bidirectional"))
    )
    (net (code "131") (name "unconnected-(U$6-PadAXI_RST)") (class "Default")
      (node (ref "U$6") (pin "AXI_RST") (pinfunction "AXI_RST_AXI_RST") (pintype "bidirectional"))
    )
    (net (code "132") (name "unconnected-(U$6-PadDAC_AXI_OUT)") (class "Default")
      (node (ref "U$6") (pin "DAC_AXI_OUT") (pinfunction "DAC_AXI_OUT_DAC_AXI_OUT") (pintype "bidirectional"))
    )
    (net (code "133") (name "unconnected-(U$6-PadGPIO00_PAD)") (class "Default")
      (node (ref "U$6") (pin "GPIO00_PAD") (pinfunction "GPIO00_PAD_GPIO00_PAD") (pintype "bidirectional"))
    )
    (net (code "134") (name "unconnected-(U$6-PadGPIO01_PAD)") (class "Default")
      (node (ref "U$6") (pin "GPIO01_PAD") (pinfunction "GPIO01_PAD_GPIO01_PAD") (pintype "bidirectional"))
    )
    (net (code "135") (name "unconnected-(U$6-PadGPIO02_PAD)") (class "Default")
      (node (ref "U$6") (pin "GPIO02_PAD") (pinfunction "GPIO02_PAD_GPIO02_PAD") (pintype "bidirectional"))
    )
    (net (code "136") (name "unconnected-(U$6-PadGPIO03_PAD)") (class "Default")
      (node (ref "U$6") (pin "GPIO03_PAD") (pinfunction "GPIO03_PAD_GPIO03_PAD") (pintype "bidirectional"))
    )
    (net (code "137") (name "unconnected-(U$6-PadGPIO04_PAD)") (class "Default")
      (node (ref "U$6") (pin "GPIO04_PAD") (pinfunction "GPIO04_PAD_GPIO04_PAD") (pintype "bidirectional"))
    )
    (net (code "138") (name "unconnected-(U$6-PadGPIO05_PAD)") (class "Default")
      (node (ref "U$6") (pin "GPIO05_PAD") (pinfunction "GPIO05_PAD_GPIO05_PAD") (pintype "bidirectional"))
    )
    (net (code "139") (name "unconnected-(U$6-PadGPIO06_PAD)") (class "Default")
      (node (ref "U$6") (pin "GPIO06_PAD") (pinfunction "GPIO06_PAD_GPIO06_PAD") (pintype "bidirectional"))
    )
    (net (code "140") (name "unconnected-(U$6-PadGPIO07_PAD)") (class "Default")
      (node (ref "U$6") (pin "GPIO07_PAD") (pinfunction "GPIO07_PAD_GPIO07_PAD") (pintype "bidirectional"))
    )
    (net (code "141") (name "unconnected-(U$6-PadH_CEB)") (class "Default")
      (node (ref "U$6") (pin "H_CEB") (pinfunction "H_CEB_H_CEB") (pintype "bidirectional"))
    )
    (net (code "142") (name "unconnected-(U$6-PadH_CLK)") (class "Default")
      (node (ref "U$6") (pin "H_CLK") (pinfunction "H_CLK_H_CLK") (pintype "bidirectional"))
    )
    (net (code "143") (name "unconnected-(U$6-PadH_CLK_10)") (class "Default")
      (node (ref "U$6") (pin "H_CLK_10") (pinfunction "H_CLK_10_H_CLK_10") (pintype "bidirectional"))
    )
    (net (code "144") (name "unconnected-(U$6-PadH_CLK_200)") (class "Default")
      (node (ref "U$6") (pin "H_CLK_200") (pinfunction "H_CLK_200_H_CLK_200") (pintype "bidirectional"))
    )
    (net (code "145") (name "unconnected-(U$6-PadH_DATA)") (class "Default")
      (node (ref "U$6") (pin "H_DATA") (pinfunction "H_DATA_H_DATA") (pintype "bidirectional"))
    )
    (net (code "146") (name "unconnected-(U$6-PadH_DOUT)") (class "Default")
      (node (ref "U$6") (pin "H_DOUT") (pinfunction "H_DOUT_H_DOUT") (pintype "bidirectional"))
    )
    (net (code "147") (name "unconnected-(U$6-PadH_RST)") (class "Default")
      (node (ref "U$6") (pin "H_RST") (pinfunction "H_RST_H_RST") (pintype "bidirectional"))
    )
    (net (code "148") (name "unconnected-(U$6-PadSPI_AXI_MASTER_CEB)") (class "Default")
      (node (ref "U$6") (pin "SPI_AXI_MASTER_CEB") (pinfunction "SPI_AXI_MASTER_CEB_SPI_AXI_MASTER_CEB") (pintype "bidirectional"))
    )
    (net (code "149") (name "unconnected-(U$6-PadSPI_AXI_MASTER_DATA)") (class "Default")
      (node (ref "U$6") (pin "SPI_AXI_MASTER_DATA") (pinfunction "SPI_AXI_MASTER_DATA_SPI_AXI_MASTER_DATA") (pintype "bidirectional"))
    )
    (net (code "150") (name "unconnected-(U$6-PadSPI_AXI_MASTER_DOUT)") (class "Default")
      (node (ref "U$6") (pin "SPI_AXI_MASTER_DOUT") (pinfunction "SPI_AXI_MASTER_DOUT_SPI_AXI_MASTER_DOUT") (pintype "bidirectional"))
    )
    (net (code "151") (name "unconnected-(U$6-PadSPI_AXI_MASTER_SCLK)") (class "Default")
      (node (ref "U$6") (pin "SPI_AXI_MASTER_SCLK") (pinfunction "SPI_AXI_MASTER_SCLK_SPI_AXI_MASTER_SCLK") (pintype "bidirectional"))
    )
    (net (code "152") (name "unconnected-(U$6-PadSPI_AXI_SLAVE_CEB)") (class "Default")
      (node (ref "U$6") (pin "SPI_AXI_SLAVE_CEB") (pinfunction "SPI_AXI_SLAVE_CEB_SPI_AXI_SLAVE_CEB") (pintype "bidirectional"))
    )
    (net (code "153") (name "unconnected-(U$6-PadSPI_AXI_SLAVE_DATA)") (class "Default")
      (node (ref "U$6") (pin "SPI_AXI_SLAVE_DATA") (pinfunction "SPI_AXI_SLAVE_DATA_SPI_AXI_SLAVE_DATA") (pintype "bidirectional"))
    )
    (net (code "154") (name "unconnected-(U$6-PadSPI_AXI_SLAVE_SCLK)") (class "Default")
      (node (ref "U$6") (pin "SPI_AXI_SLAVE_SCLK") (pinfunction "SPI_AXI_SLAVE_SCLK_SPI_AXI_SLAVE_SCLK") (pintype "bidirectional"))
    )
    (net (code "155") (name "unconnected-(U$6-PadVDDPOC)") (class "Default")
      (node (ref "U$6") (pin "VDDPOC") (pinfunction "VDDPOC_VDDPOC") (pintype "bidirectional"))
    )
    (net (code "156") (name "unconnected-(U$6-PadVDDPST)") (class "Default")
      (node (ref "U$6") (pin "VDDPST") (pinfunction "VDDPST_VDDPST") (pintype "bidirectional"))
    )
    (net (code "157") (name "unconnected-(U$6-PadVREF_ADC)") (class "Default")
      (node (ref "U$6") (pin "VREF_ADC") (pinfunction "VREF_ADC_VREF_ADC") (pintype "bidirectional"))
    )
    (net (code "158") (name "unconnected-(U$6-PadVREF_DAC)") (class "Default")
      (node (ref "U$6") (pin "VREF_DAC") (pinfunction "VREF_DAC_VREF_DAC") (pintype "bidirectional"))
    )
    (net (code "159") (name "unconnected-(U$6-VDD-PadVDD@1)") (class "Default")
      (node (ref "U$6") (pin "VDD@1") (pinfunction "VDD_VDD@1") (pintype "bidirectional"))
    )
    (net (code "160") (name "unconnected-(U$6-VDD-PadVDD@2)") (class "Default")
      (node (ref "U$6") (pin "VDD@2") (pinfunction "VDD_VDD@2") (pintype "bidirectional"))
    )
    (net (code "161") (name "unconnected-(U$6-VDD-PadVDD@3)") (class "Default")
      (node (ref "U$6") (pin "VDD@3") (pinfunction "VDD_VDD@3") (pintype "bidirectional"))
    )
    (net (code "162") (name "unconnected-(U$6-VDD-PadVDD@4)") (class "Default")
      (node (ref "U$6") (pin "VDD@4") (pinfunction "VDD_VDD@4") (pintype "bidirectional"))
    )
    (net (code "163") (name "unconnected-(U$6-VDD-PadVDD@5)") (class "Default")
      (node (ref "U$6") (pin "VDD@5") (pinfunction "VDD_VDD@5") (pintype "bidirectional"))
    )
    (net (code "164") (name "unconnected-(U$6-VSS-PadVSS@1)") (class "Default")
      (node (ref "U$6") (pin "VSS@1") (pinfunction "VSS_VSS@1") (pintype "bidirectional"))
    )
    (net (code "165") (name "unconnected-(U$6-VSS-PadVSS@2)") (class "Default")
      (node (ref "U$6") (pin "VSS@2") (pinfunction "VSS_VSS@2") (pintype "bidirectional"))
    )
    (net (code "166") (name "unconnected-(U$6-VSS-PadVSS@3)") (class "Default")
      (node (ref "U$6") (pin "VSS@3") (pinfunction "VSS_VSS@3") (pintype "bidirectional"))
    )
    (net (code "167") (name "unconnected-(U$6-VSS-PadVSS@4)") (class "Default")
      (node (ref "U$6") (pin "VSS@4") (pinfunction "VSS_VSS@4") (pintype "bidirectional"))
    )
    (net (code "168") (name "unconnected-(U$6-VSS-PadVSS@5)") (class "Default")
      (node (ref "U$6") (pin "VSS@5") (pinfunction "VSS_VSS@5") (pintype "bidirectional"))
    )
    (net (code "169") (name "unconnected-(U$6-VSS-PadVSS@6)") (class "Default")
      (node (ref "U$6") (pin "VSS@6") (pinfunction "VSS_VSS@6") (pintype "bidirectional"))
    )
    (net (code "170") (name "unconnected-(U$6-VSS-PadVSS@7)") (class "Default")
      (node (ref "U$6") (pin "VSS@7") (pinfunction "VSS_VSS@7") (pintype "bidirectional"))
    )
    (net (code "171") (name "unconnected-(U$6-VSS-PadVSS@8)") (class "Default")
      (node (ref "U$6") (pin "VSS@8") (pinfunction "VSS_VSS@8") (pintype "bidirectional"))
    )
    (net (code "172") (name "unconnected-(U$6-VSSPST-PadN$10000)") (class "Default")
      (node (ref "U$6") (pin "N$10000") (pinfunction "VSSPST_N$10000") (pintype "bidirectional"))
    )
    (net (code "173") (name "unconnected-(U$6-VSSPST-PadVSSPST@2)") (class "Default")
      (node (ref "U$6") (pin "VSSPST@2") (pinfunction "VSSPST_VSSPST@2") (pintype "bidirectional"))
    )
    (net (code "174") (name "unconnected-(U$7-AVDD-PadAVDD@1)") (class "Default")
      (node (ref "U$7") (pin "AVDD@1") (pinfunction "AVDD_AVDD@1") (pintype "bidirectional"))
    )
    (net (code "175") (name "unconnected-(U$7-AVDD-PadAVDD@2)") (class "Default")
      (node (ref "U$7") (pin "AVDD@2") (pinfunction "AVDD_AVDD@2") (pintype "bidirectional"))
    )
    (net (code "176") (name "unconnected-(U$7-AVSS-PadAVSS@1)") (class "Default")
      (node (ref "U$7") (pin "AVSS@1") (pinfunction "AVSS_AVSS@1") (pintype "bidirectional"))
    )
    (net (code "177") (name "unconnected-(U$7-AVSS-PadAVSS@2)") (class "Default")
      (node (ref "U$7") (pin "AVSS@2") (pinfunction "AVSS_AVSS@2") (pintype "bidirectional"))
    )
    (net (code "178") (name "unconnected-(U$7-AVSS-PadAVSS@3)") (class "Default")
      (node (ref "U$7") (pin "AVSS@3") (pinfunction "AVSS_AVSS@3") (pintype "bidirectional"))
    )
    (net (code "179") (name "unconnected-(U$7-AVSS-PadAVSS@4)") (class "Default")
      (node (ref "U$7") (pin "AVSS@4") (pinfunction "AVSS_AVSS@4") (pintype "bidirectional"))
    )
    (net (code "180") (name "unconnected-(U$7-PadADC_AXI_CLK)") (class "Default")
      (node (ref "U$7") (pin "ADC_AXI_CLK") (pinfunction "ADC_AXI_CLK_ADC_AXI_CLK") (pintype "bidirectional"))
    )
    (net (code "181") (name "unconnected-(U$7-PadADC_AXI_IN)") (class "Default")
      (node (ref "U$7") (pin "ADC_AXI_IN") (pinfunction "ADC_AXI_IN_ADC_AXI_IN") (pintype "bidirectional"))
    )
    (net (code "182") (name "unconnected-(U$7-PadADC_AXI_IP)") (class "Default")
      (node (ref "U$7") (pin "ADC_AXI_IP") (pinfunction "ADC_AXI_IP_ADC_AXI_IP") (pintype "bidirectional"))
    )
    (net (code "183") (name "unconnected-(U$7-PadADC_AXI_RST)") (class "Default")
      (node (ref "U$7") (pin "ADC_AXI_RST") (pinfunction "ADC_AXI_RST_ADC_AXI_RST") (pintype "bidirectional"))
    )
    (net (code "184") (name "unconnected-(U$7-PadAXI_CLK)") (class "Default")
      (node (ref "U$7") (pin "AXI_CLK") (pinfunction "AXI_CLK_AXI_CLK") (pintype "bidirectional"))
    )
    (net (code "185") (name "unconnected-(U$7-PadAXI_RST)") (class "Default")
      (node (ref "U$7") (pin "AXI_RST") (pinfunction "AXI_RST_AXI_RST") (pintype "bidirectional"))
    )
    (net (code "186") (name "unconnected-(U$7-PadDAC_AXI_OUT)") (class "Default")
      (node (ref "U$7") (pin "DAC_AXI_OUT") (pinfunction "DAC_AXI_OUT_DAC_AXI_OUT") (pintype "bidirectional"))
    )
    (net (code "187") (name "unconnected-(U$7-PadGPIO00_PAD)") (class "Default")
      (node (ref "U$7") (pin "GPIO00_PAD") (pinfunction "GPIO00_PAD_GPIO00_PAD") (pintype "bidirectional"))
    )
    (net (code "188") (name "unconnected-(U$7-PadGPIO01_PAD)") (class "Default")
      (node (ref "U$7") (pin "GPIO01_PAD") (pinfunction "GPIO01_PAD_GPIO01_PAD") (pintype "bidirectional"))
    )
    (net (code "189") (name "unconnected-(U$7-PadGPIO02_PAD)") (class "Default")
      (node (ref "U$7") (pin "GPIO02_PAD") (pinfunction "GPIO02_PAD_GPIO02_PAD") (pintype "bidirectional"))
    )
    (net (code "190") (name "unconnected-(U$7-PadGPIO03_PAD)") (class "Default")
      (node (ref "U$7") (pin "GPIO03_PAD") (pinfunction "GPIO03_PAD_GPIO03_PAD") (pintype "bidirectional"))
    )
    (net (code "191") (name "unconnected-(U$7-PadGPIO04_PAD)") (class "Default")
      (node (ref "U$7") (pin "GPIO04_PAD") (pinfunction "GPIO04_PAD_GPIO04_PAD") (pintype "bidirectional"))
    )
    (net (code "192") (name "unconnected-(U$7-PadGPIO05_PAD)") (class "Default")
      (node (ref "U$7") (pin "GPIO05_PAD") (pinfunction "GPIO05_PAD_GPIO05_PAD") (pintype "bidirectional"))
    )
    (net (code "193") (name "unconnected-(U$7-PadGPIO06_PAD)") (class "Default")
      (node (ref "U$7") (pin "GPIO06_PAD") (pinfunction "GPIO06_PAD_GPIO06_PAD") (pintype "bidirectional"))
    )
    (net (code "194") (name "unconnected-(U$7-PadGPIO07_PAD)") (class "Default")
      (node (ref "U$7") (pin "GPIO07_PAD") (pinfunction "GPIO07_PAD_GPIO07_PAD") (pintype "bidirectional"))
    )
    (net (code "195") (name "unconnected-(U$7-PadH_CEB)") (class "Default")
      (node (ref "U$7") (pin "H_CEB") (pinfunction "H_CEB_H_CEB") (pintype "bidirectional"))
    )
    (net (code "196") (name "unconnected-(U$7-PadH_CLK)") (class "Default")
      (node (ref "U$7") (pin "H_CLK") (pinfunction "H_CLK_H_CLK") (pintype "bidirectional"))
    )
    (net (code "197") (name "unconnected-(U$7-PadH_CLK_10)") (class "Default")
      (node (ref "U$7") (pin "H_CLK_10") (pinfunction "H_CLK_10_H_CLK_10") (pintype "bidirectional"))
    )
    (net (code "198") (name "unconnected-(U$7-PadH_CLK_200)") (class "Default")
      (node (ref "U$7") (pin "H_CLK_200") (pinfunction "H_CLK_200_H_CLK_200") (pintype "bidirectional"))
    )
    (net (code "199") (name "unconnected-(U$7-PadH_DATA)") (class "Default")
      (node (ref "U$7") (pin "H_DATA") (pinfunction "H_DATA_H_DATA") (pintype "bidirectional"))
    )
    (net (code "200") (name "unconnected-(U$7-PadH_DOUT)") (class "Default")
      (node (ref "U$7") (pin "H_DOUT") (pinfunction "H_DOUT_H_DOUT") (pintype "bidirectional"))
    )
    (net (code "201") (name "unconnected-(U$7-PadH_RST)") (class "Default")
      (node (ref "U$7") (pin "H_RST") (pinfunction "H_RST_H_RST") (pintype "bidirectional"))
    )
    (net (code "202") (name "unconnected-(U$7-PadSPI_AXI_MASTER_CEB)") (class "Default")
      (node (ref "U$7") (pin "SPI_AXI_MASTER_CEB") (pinfunction "SPI_AXI_MASTER_CEB_SPI_AXI_MASTER_CEB") (pintype "bidirectional"))
    )
    (net (code "203") (name "unconnected-(U$7-PadSPI_AXI_MASTER_DATA)") (class "Default")
      (node (ref "U$7") (pin "SPI_AXI_MASTER_DATA") (pinfunction "SPI_AXI_MASTER_DATA_SPI_AXI_MASTER_DATA") (pintype "bidirectional"))
    )
    (net (code "204") (name "unconnected-(U$7-PadSPI_AXI_MASTER_DOUT)") (class "Default")
      (node (ref "U$7") (pin "SPI_AXI_MASTER_DOUT") (pinfunction "SPI_AXI_MASTER_DOUT_SPI_AXI_MASTER_DOUT") (pintype "bidirectional"))
    )
    (net (code "205") (name "unconnected-(U$7-PadSPI_AXI_MASTER_SCLK)") (class "Default")
      (node (ref "U$7") (pin "SPI_AXI_MASTER_SCLK") (pinfunction "SPI_AXI_MASTER_SCLK_SPI_AXI_MASTER_SCLK") (pintype "bidirectional"))
    )
    (net (code "206") (name "unconnected-(U$7-PadSPI_AXI_SLAVE_CEB)") (class "Default")
      (node (ref "U$7") (pin "SPI_AXI_SLAVE_CEB") (pinfunction "SPI_AXI_SLAVE_CEB_SPI_AXI_SLAVE_CEB") (pintype "bidirectional"))
    )
    (net (code "207") (name "unconnected-(U$7-PadSPI_AXI_SLAVE_DATA)") (class "Default")
      (node (ref "U$7") (pin "SPI_AXI_SLAVE_DATA") (pinfunction "SPI_AXI_SLAVE_DATA_SPI_AXI_SLAVE_DATA") (pintype "bidirectional"))
    )
    (net (code "208") (name "unconnected-(U$7-PadSPI_AXI_SLAVE_SCLK)") (class "Default")
      (node (ref "U$7") (pin "SPI_AXI_SLAVE_SCLK") (pinfunction "SPI_AXI_SLAVE_SCLK_SPI_AXI_SLAVE_SCLK") (pintype "bidirectional"))
    )
    (net (code "209") (name "unconnected-(U$7-PadVDDPOC)") (class "Default")
      (node (ref "U$7") (pin "VDDPOC") (pinfunction "VDDPOC_VDDPOC") (pintype "bidirectional"))
    )
    (net (code "210") (name "unconnected-(U$7-PadVDDPST)") (class "Default")
      (node (ref "U$7") (pin "VDDPST") (pinfunction "VDDPST_VDDPST") (pintype "bidirectional"))
    )
    (net (code "211") (name "unconnected-(U$7-PadVREF_ADC)") (class "Default")
      (node (ref "U$7") (pin "VREF_ADC") (pinfunction "VREF_ADC_VREF_ADC") (pintype "bidirectional"))
    )
    (net (code "212") (name "unconnected-(U$7-PadVREF_DAC)") (class "Default")
      (node (ref "U$7") (pin "VREF_DAC") (pinfunction "VREF_DAC_VREF_DAC") (pintype "bidirectional"))
    )
    (net (code "213") (name "unconnected-(U$7-VDD-PadVDD@1)") (class "Default")
      (node (ref "U$7") (pin "VDD@1") (pinfunction "VDD_VDD@1") (pintype "bidirectional"))
    )
    (net (code "214") (name "unconnected-(U$7-VDD-PadVDD@2)") (class "Default")
      (node (ref "U$7") (pin "VDD@2") (pinfunction "VDD_VDD@2") (pintype "bidirectional"))
    )
    (net (code "215") (name "unconnected-(U$7-VDD-PadVDD@3)") (class "Default")
      (node (ref "U$7") (pin "VDD@3") (pinfunction "VDD_VDD@3") (pintype "bidirectional"))
    )
    (net (code "216") (name "unconnected-(U$7-VDD-PadVDD@4)") (class "Default")
      (node (ref "U$7") (pin "VDD@4") (pinfunction "VDD_VDD@4") (pintype "bidirectional"))
    )
    (net (code "217") (name "unconnected-(U$7-VDD-PadVDD@5)") (class "Default")
      (node (ref "U$7") (pin "VDD@5") (pinfunction "VDD_VDD@5") (pintype "bidirectional"))
    )
    (net (code "218") (name "unconnected-(U$7-VSS-PadVSS@1)") (class "Default")
      (node (ref "U$7") (pin "VSS@1") (pinfunction "VSS_VSS@1") (pintype "bidirectional"))
    )
    (net (code "219") (name "unconnected-(U$7-VSS-PadVSS@2)") (class "Default")
      (node (ref "U$7") (pin "VSS@2") (pinfunction "VSS_VSS@2") (pintype "bidirectional"))
    )
    (net (code "220") (name "unconnected-(U$7-VSS-PadVSS@3)") (class "Default")
      (node (ref "U$7") (pin "VSS@3") (pinfunction "VSS_VSS@3") (pintype "bidirectional"))
    )
    (net (code "221") (name "unconnected-(U$7-VSS-PadVSS@4)") (class "Default")
      (node (ref "U$7") (pin "VSS@4") (pinfunction "VSS_VSS@4") (pintype "bidirectional"))
    )
    (net (code "222") (name "unconnected-(U$7-VSS-PadVSS@5)") (class "Default")
      (node (ref "U$7") (pin "VSS@5") (pinfunction "VSS_VSS@5") (pintype "bidirectional"))
    )
    (net (code "223") (name "unconnected-(U$7-VSS-PadVSS@6)") (class "Default")
      (node (ref "U$7") (pin "VSS@6") (pinfunction "VSS_VSS@6") (pintype "bidirectional"))
    )
    (net (code "224") (name "unconnected-(U$7-VSS-PadVSS@7)") (class "Default")
      (node (ref "U$7") (pin "VSS@7") (pinfunction "VSS_VSS@7") (pintype "bidirectional"))
    )
    (net (code "225") (name "unconnected-(U$7-VSS-PadVSS@8)") (class "Default")
      (node (ref "U$7") (pin "VSS@8") (pinfunction "VSS_VSS@8") (pintype "bidirectional"))
    )
    (net (code "226") (name "unconnected-(U$7-VSSPST-PadN$10000)") (class "Default")
      (node (ref "U$7") (pin "N$10000") (pinfunction "VSSPST_N$10000") (pintype "bidirectional"))
    )
    (net (code "227") (name "unconnected-(U$7-VSSPST-PadVSSPST@2)") (class "Default")
      (node (ref "U$7") (pin "VSSPST@2") (pinfunction "VSSPST_VSSPST@2") (pintype "bidirectional"))
    )
    (net (code "228") (name "unconnected-(X7-PadD+)") (class "Default")
      (node (ref "X7") (pin "D+") (pinfunction "D+_D+") (pintype "bidirectional"))
    )
    (net (code "229") (name "unconnected-(X7-PadD-)") (class "Default")
      (node (ref "X7") (pin "D-") (pinfunction "D-_D-") (pintype "bidirectional"))
    )
  )
)
